# OpenROV_Controller_2_5B.net
KiCad netlist of a schematic drawn in EAGLE
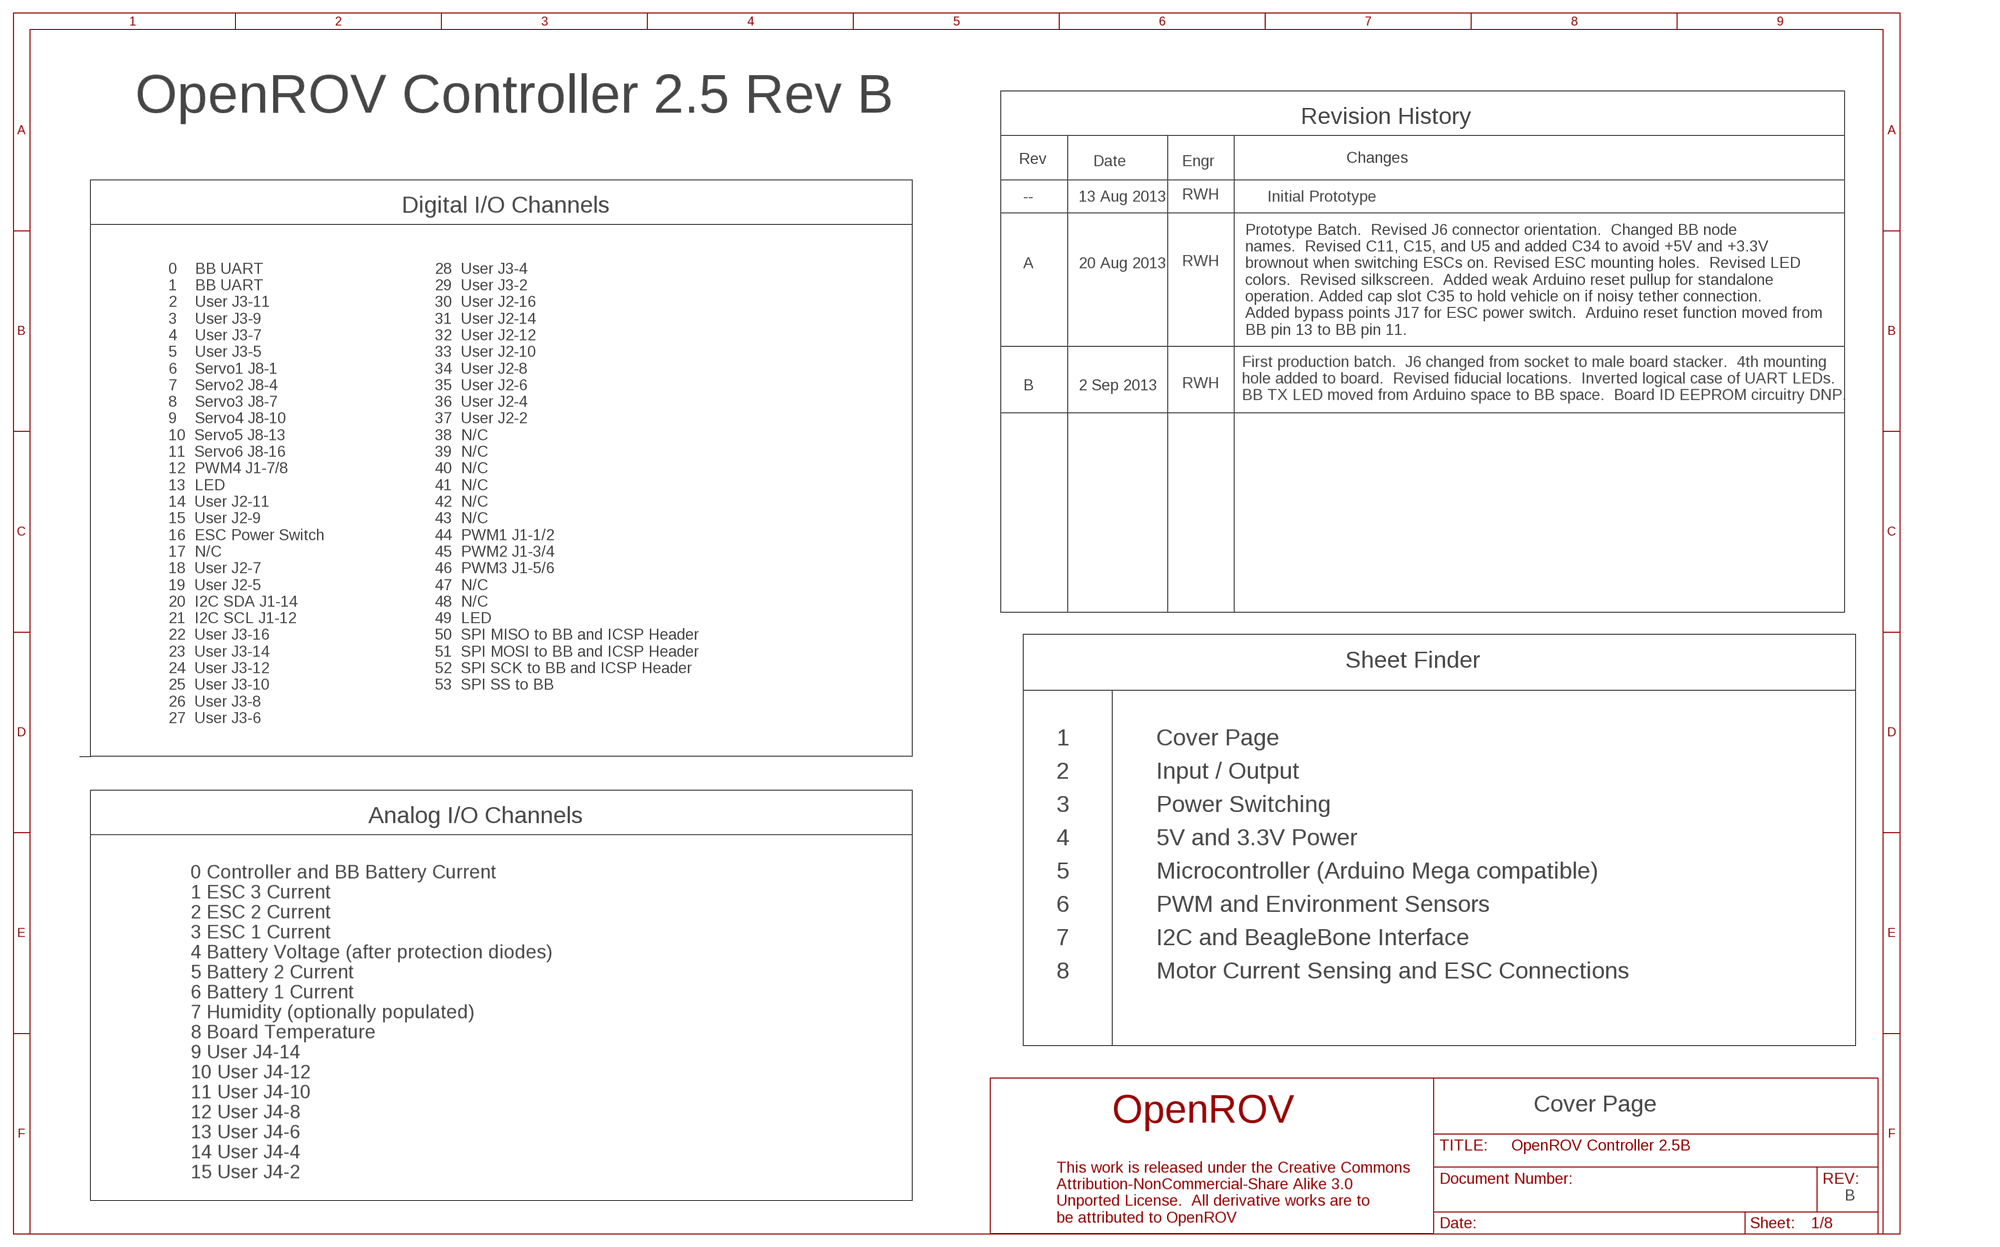
[diagram p0: schematic, sheet 1]
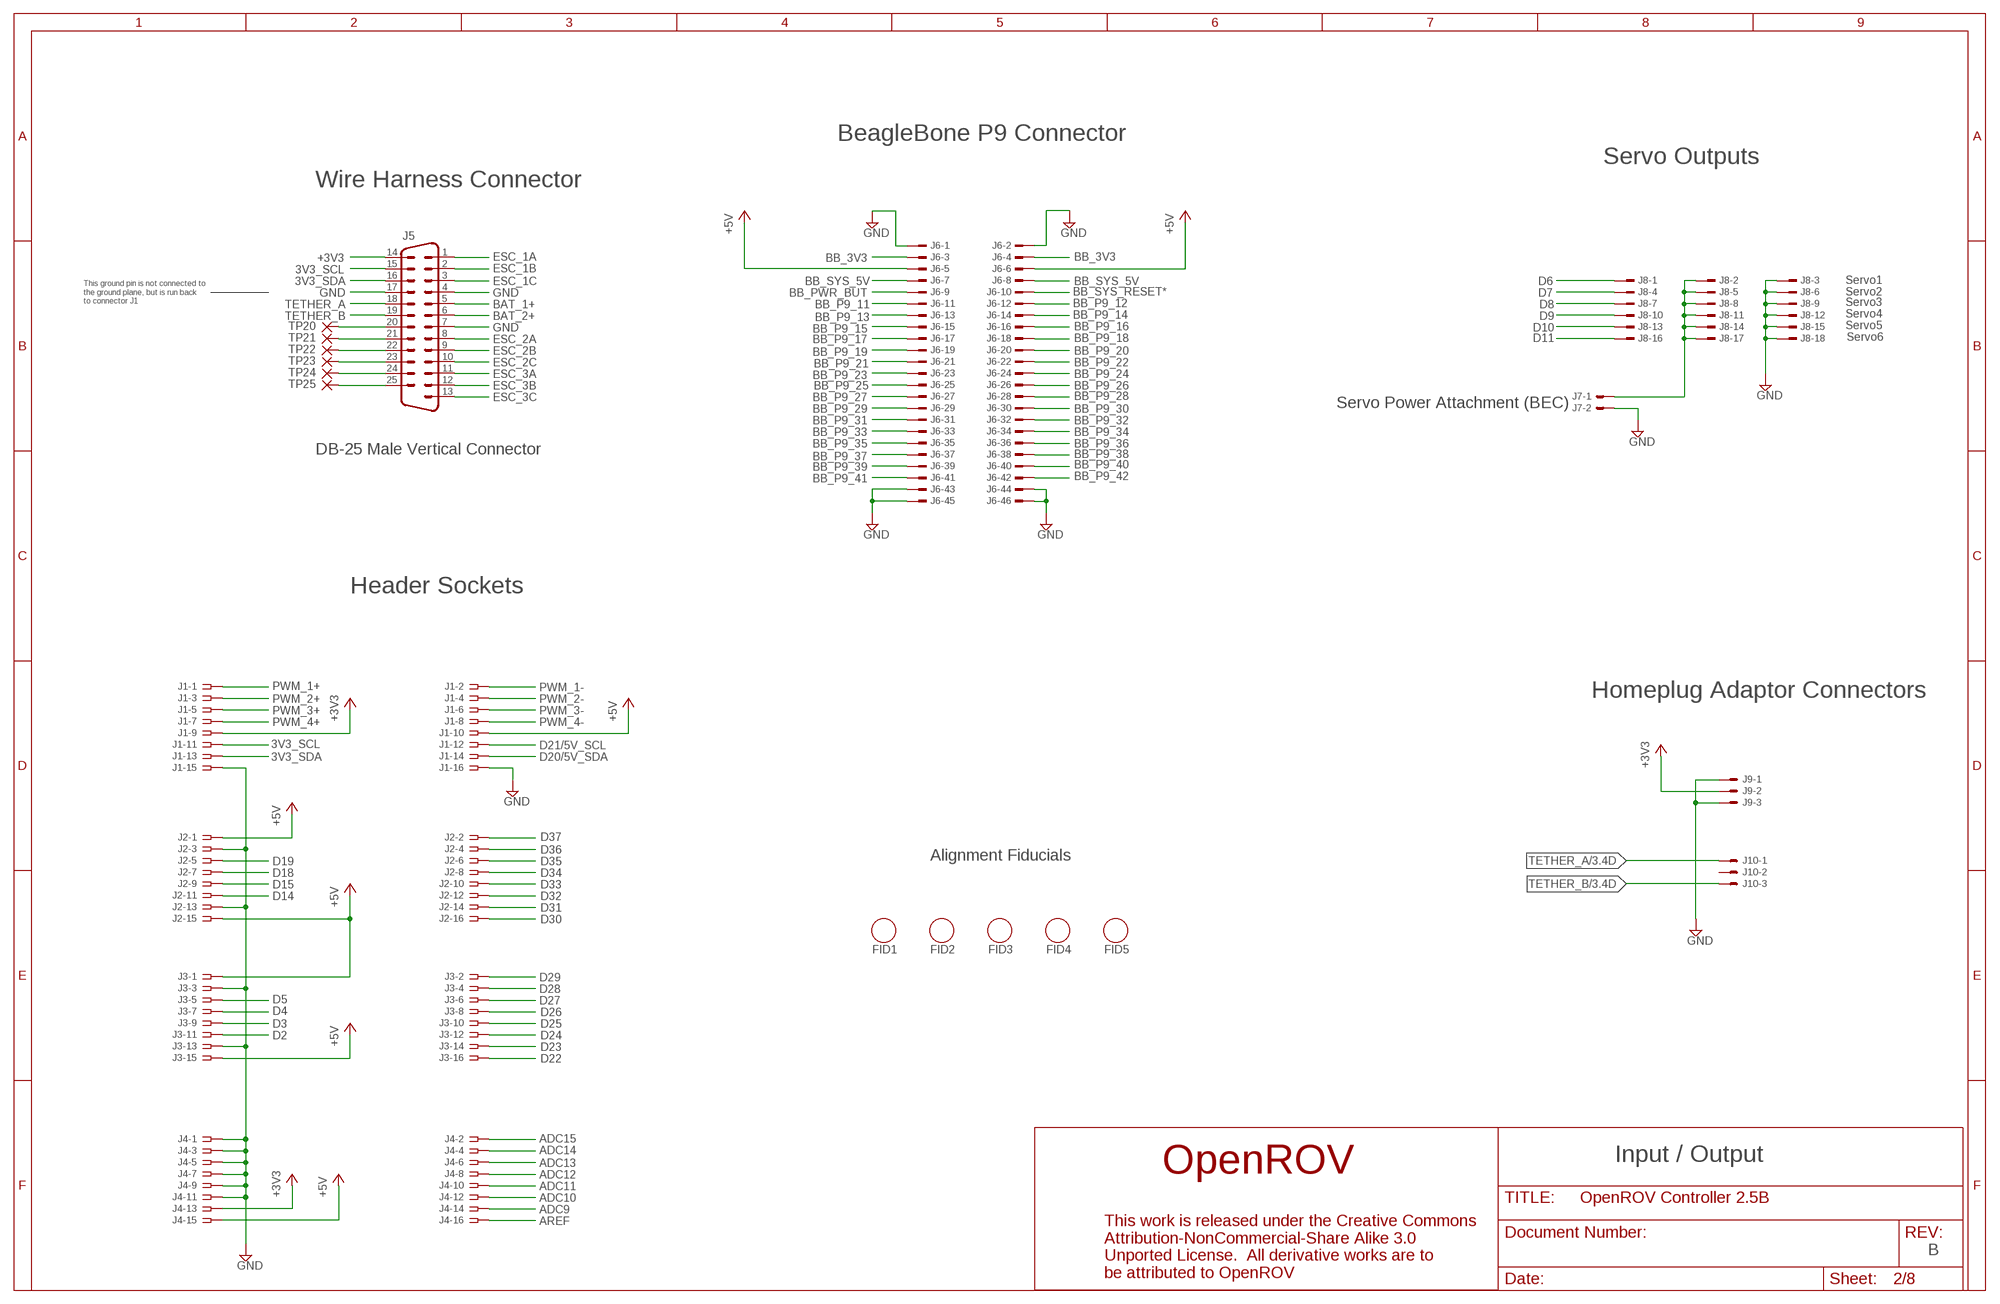
[diagram p1: schematic, sheet 2]
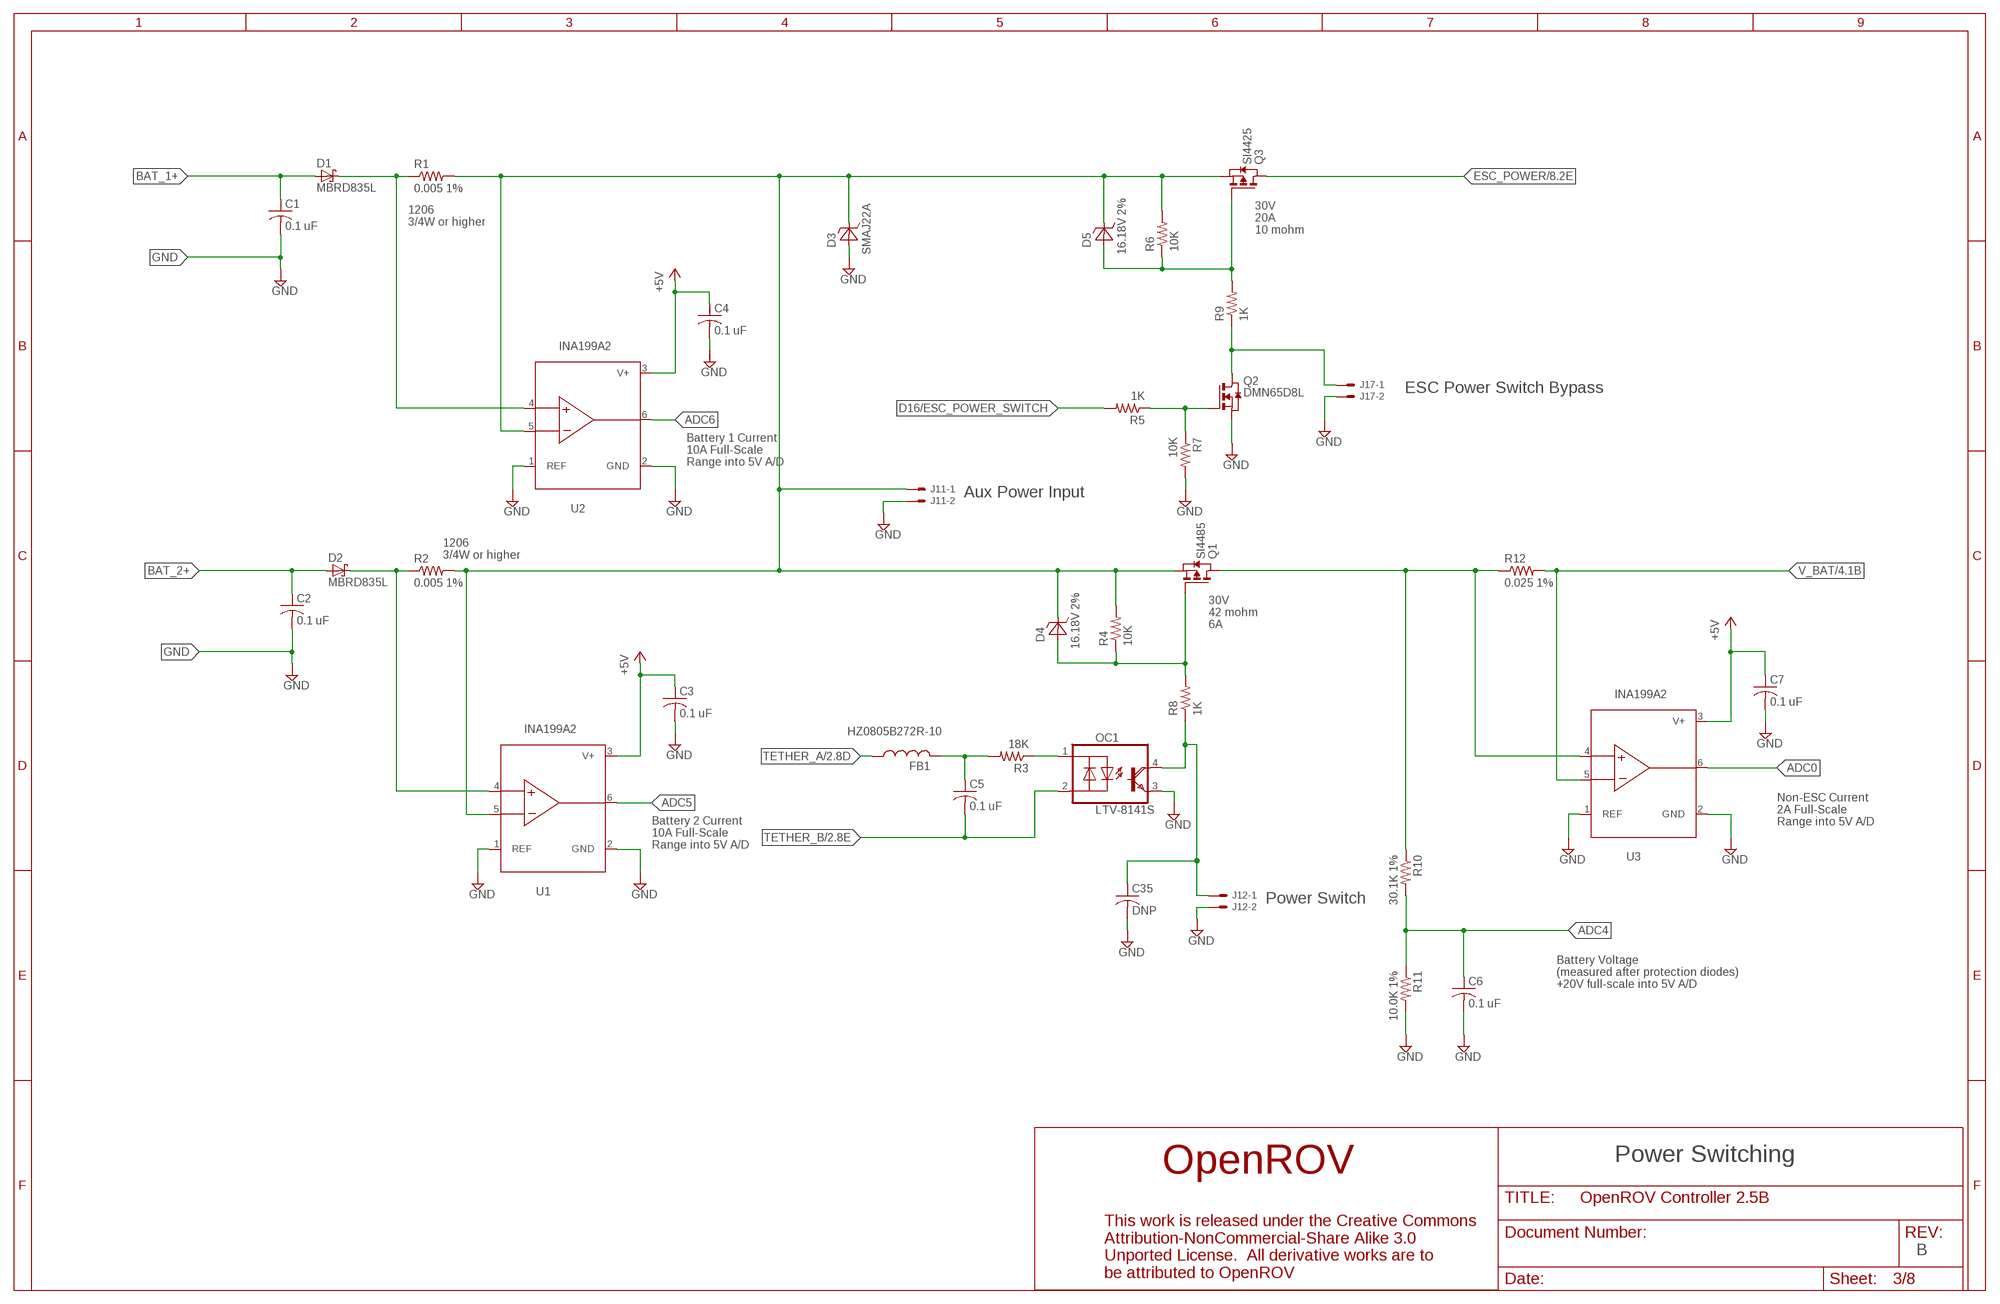
[diagram p2: schematic, sheet 3]
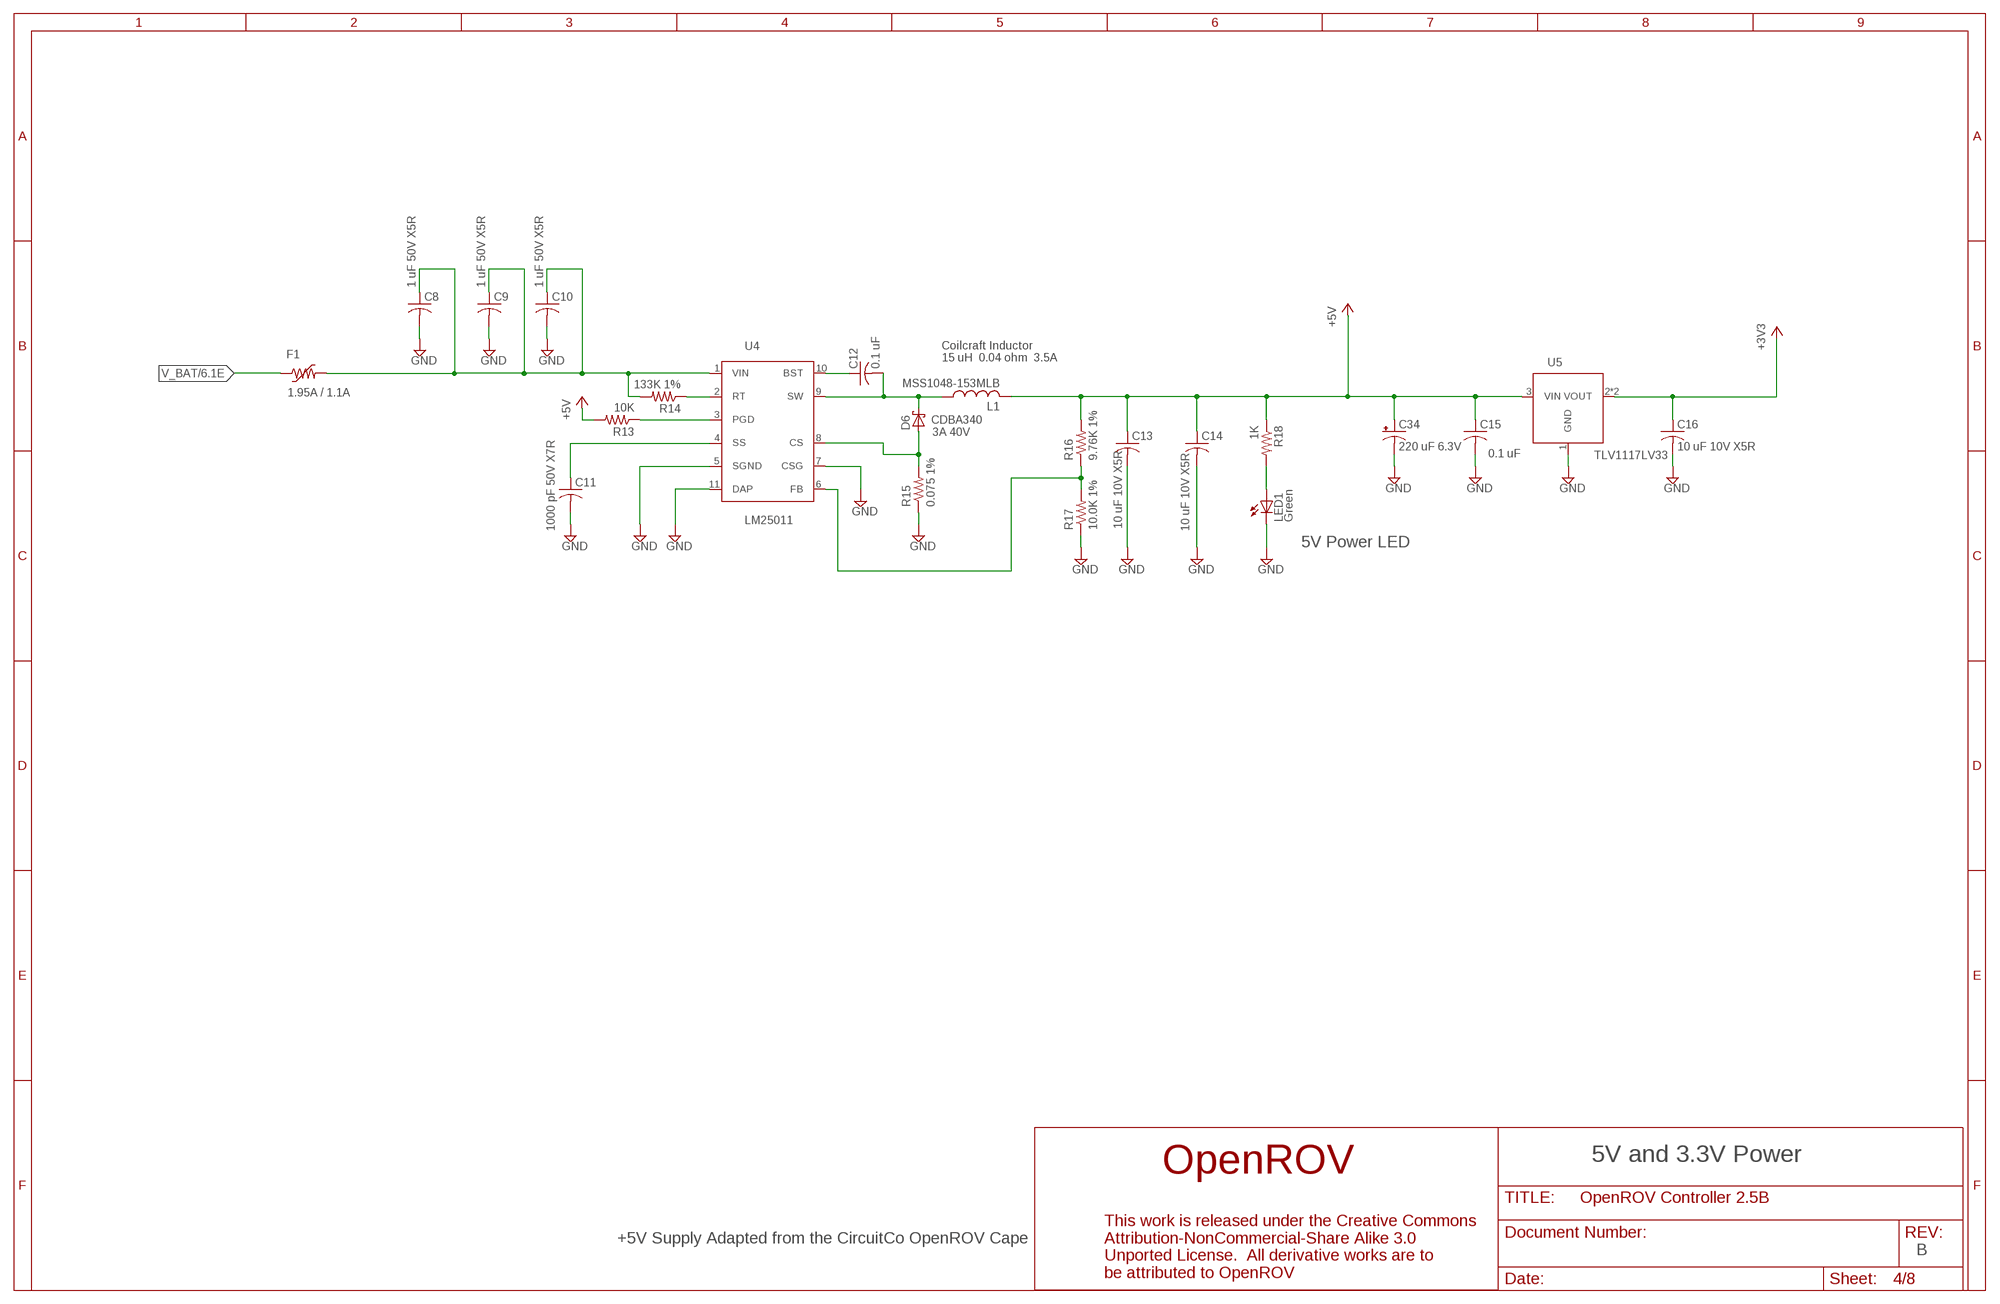
[diagram p3: schematic, sheet 4]
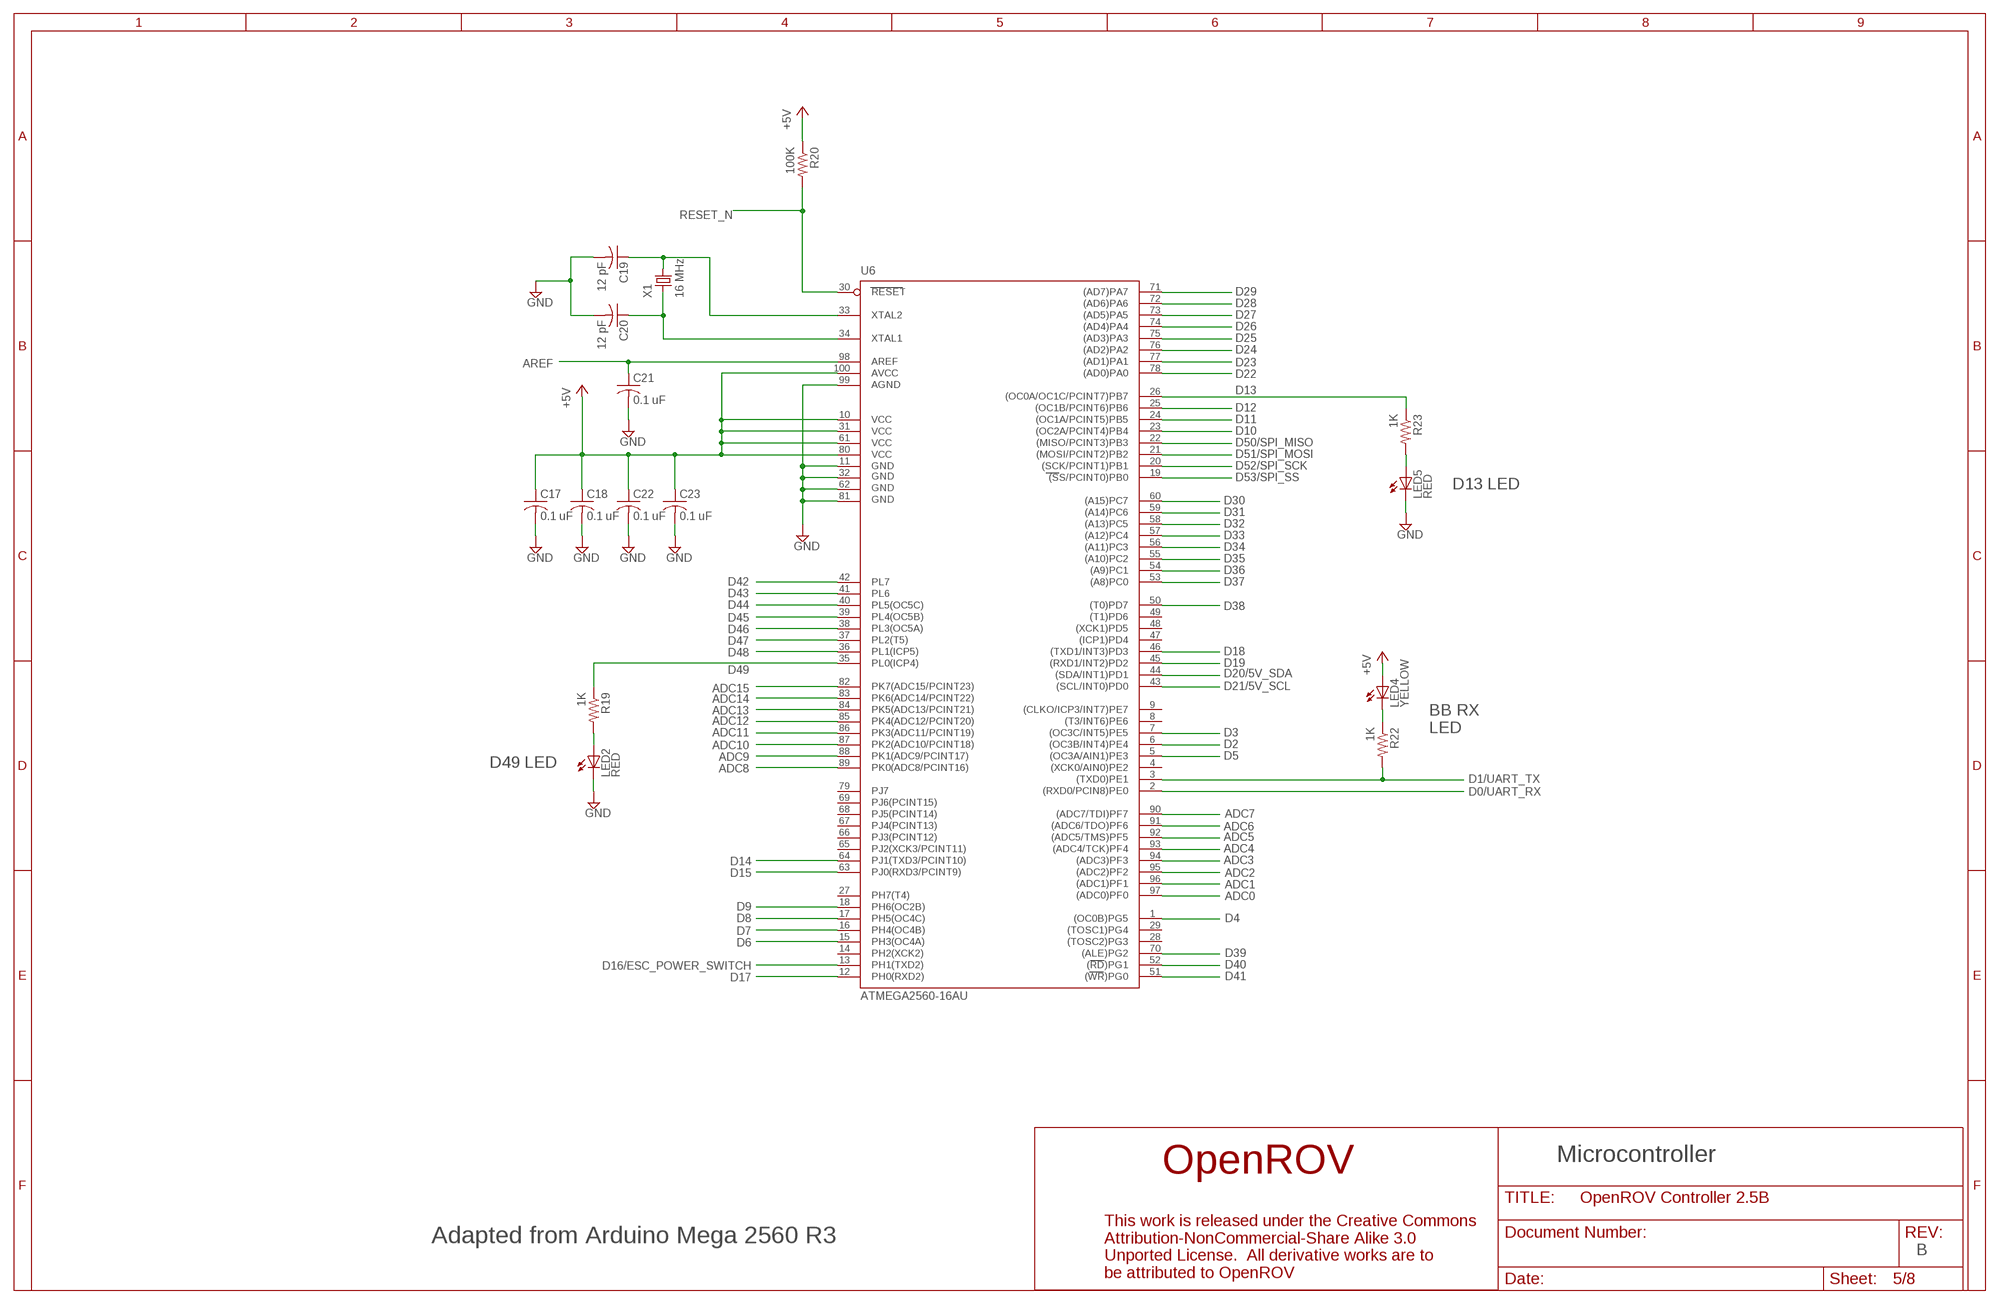
[diagram p4: schematic, sheet 5]
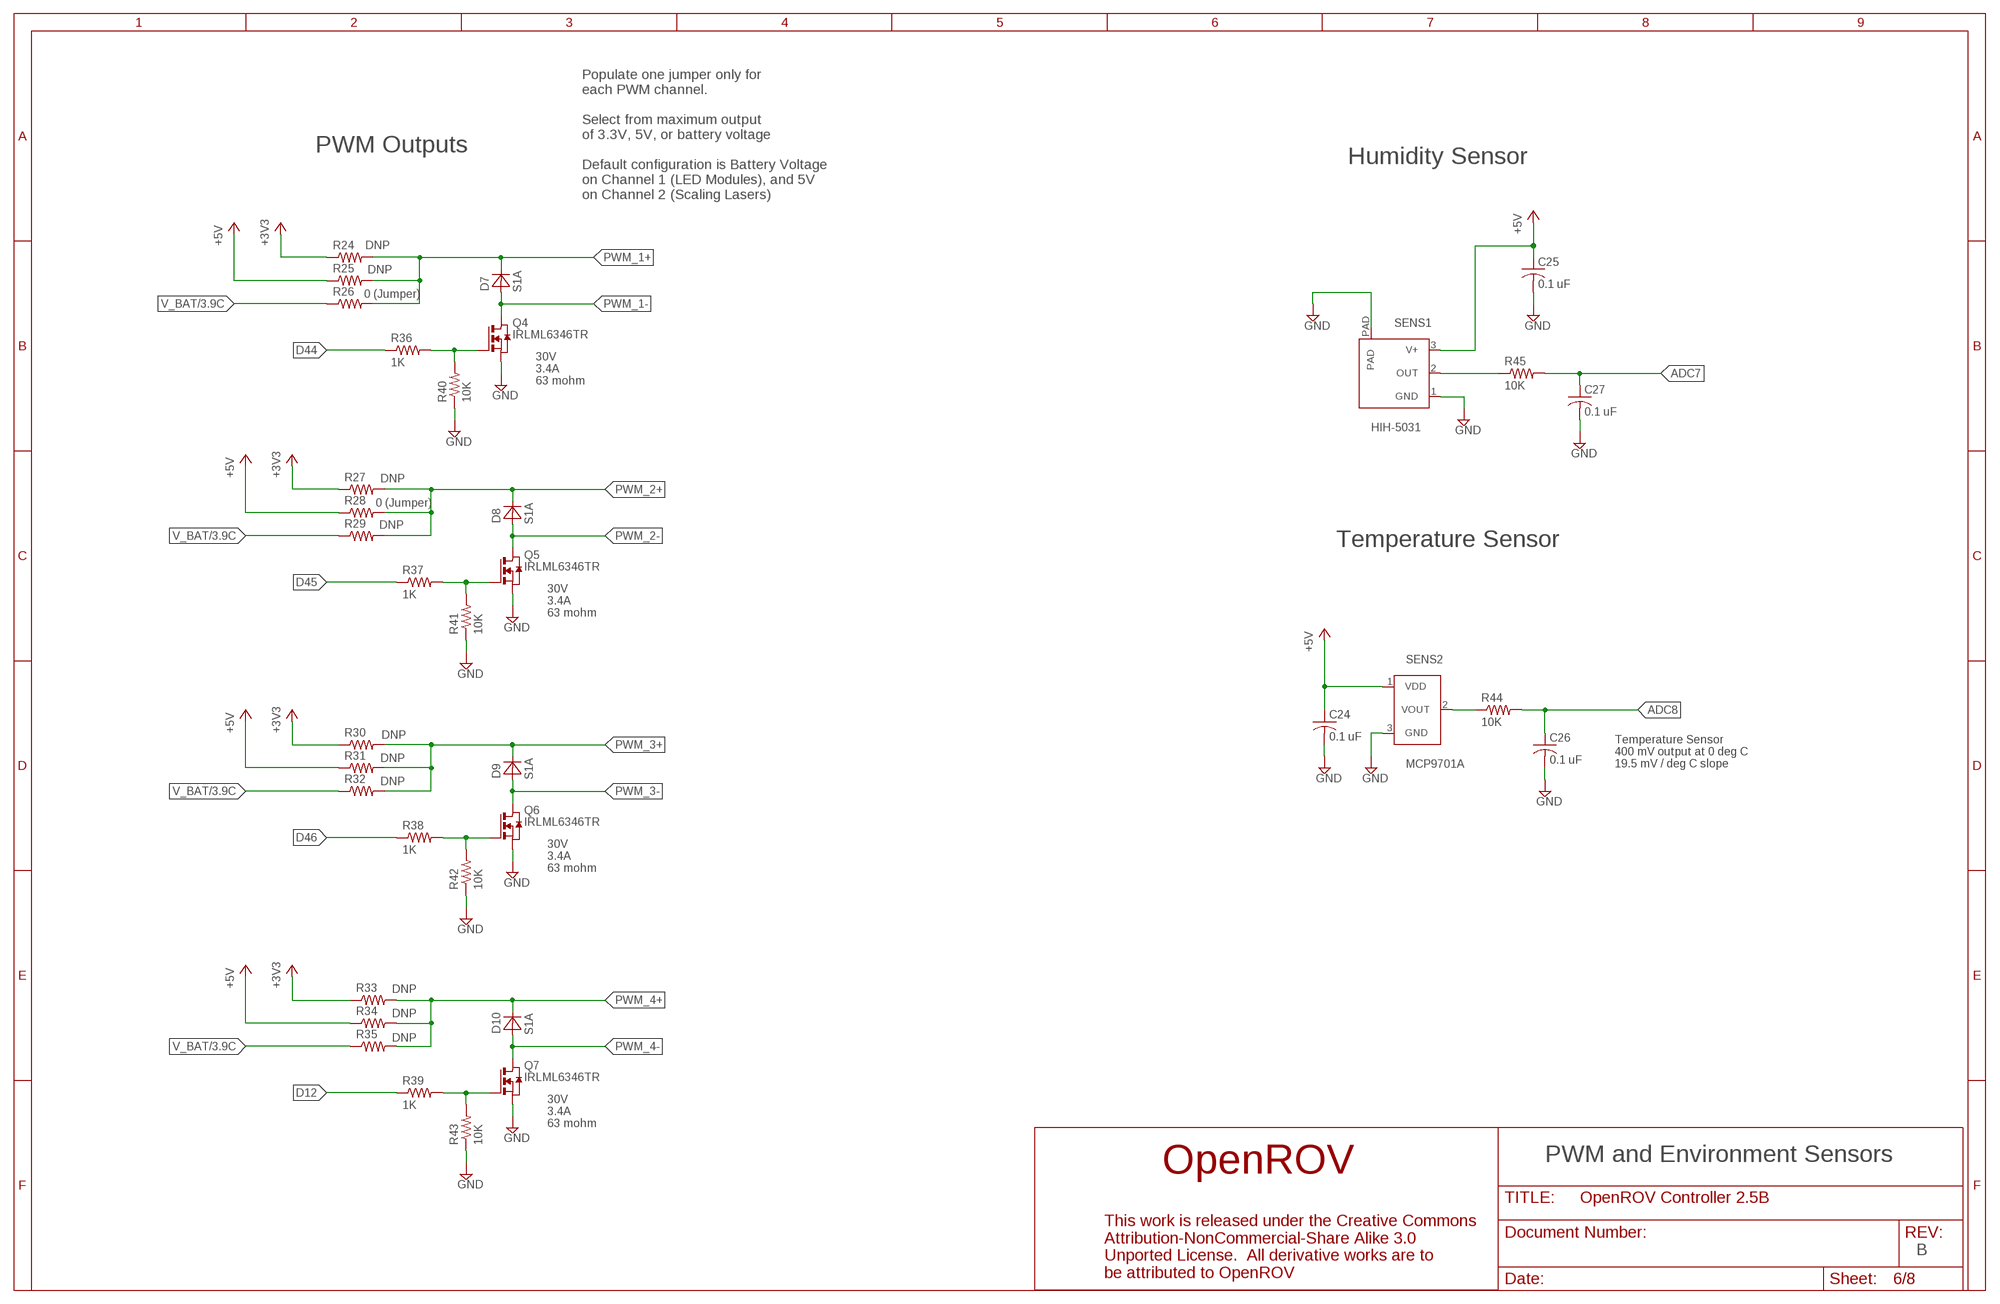
[diagram p5: schematic, sheet 6]
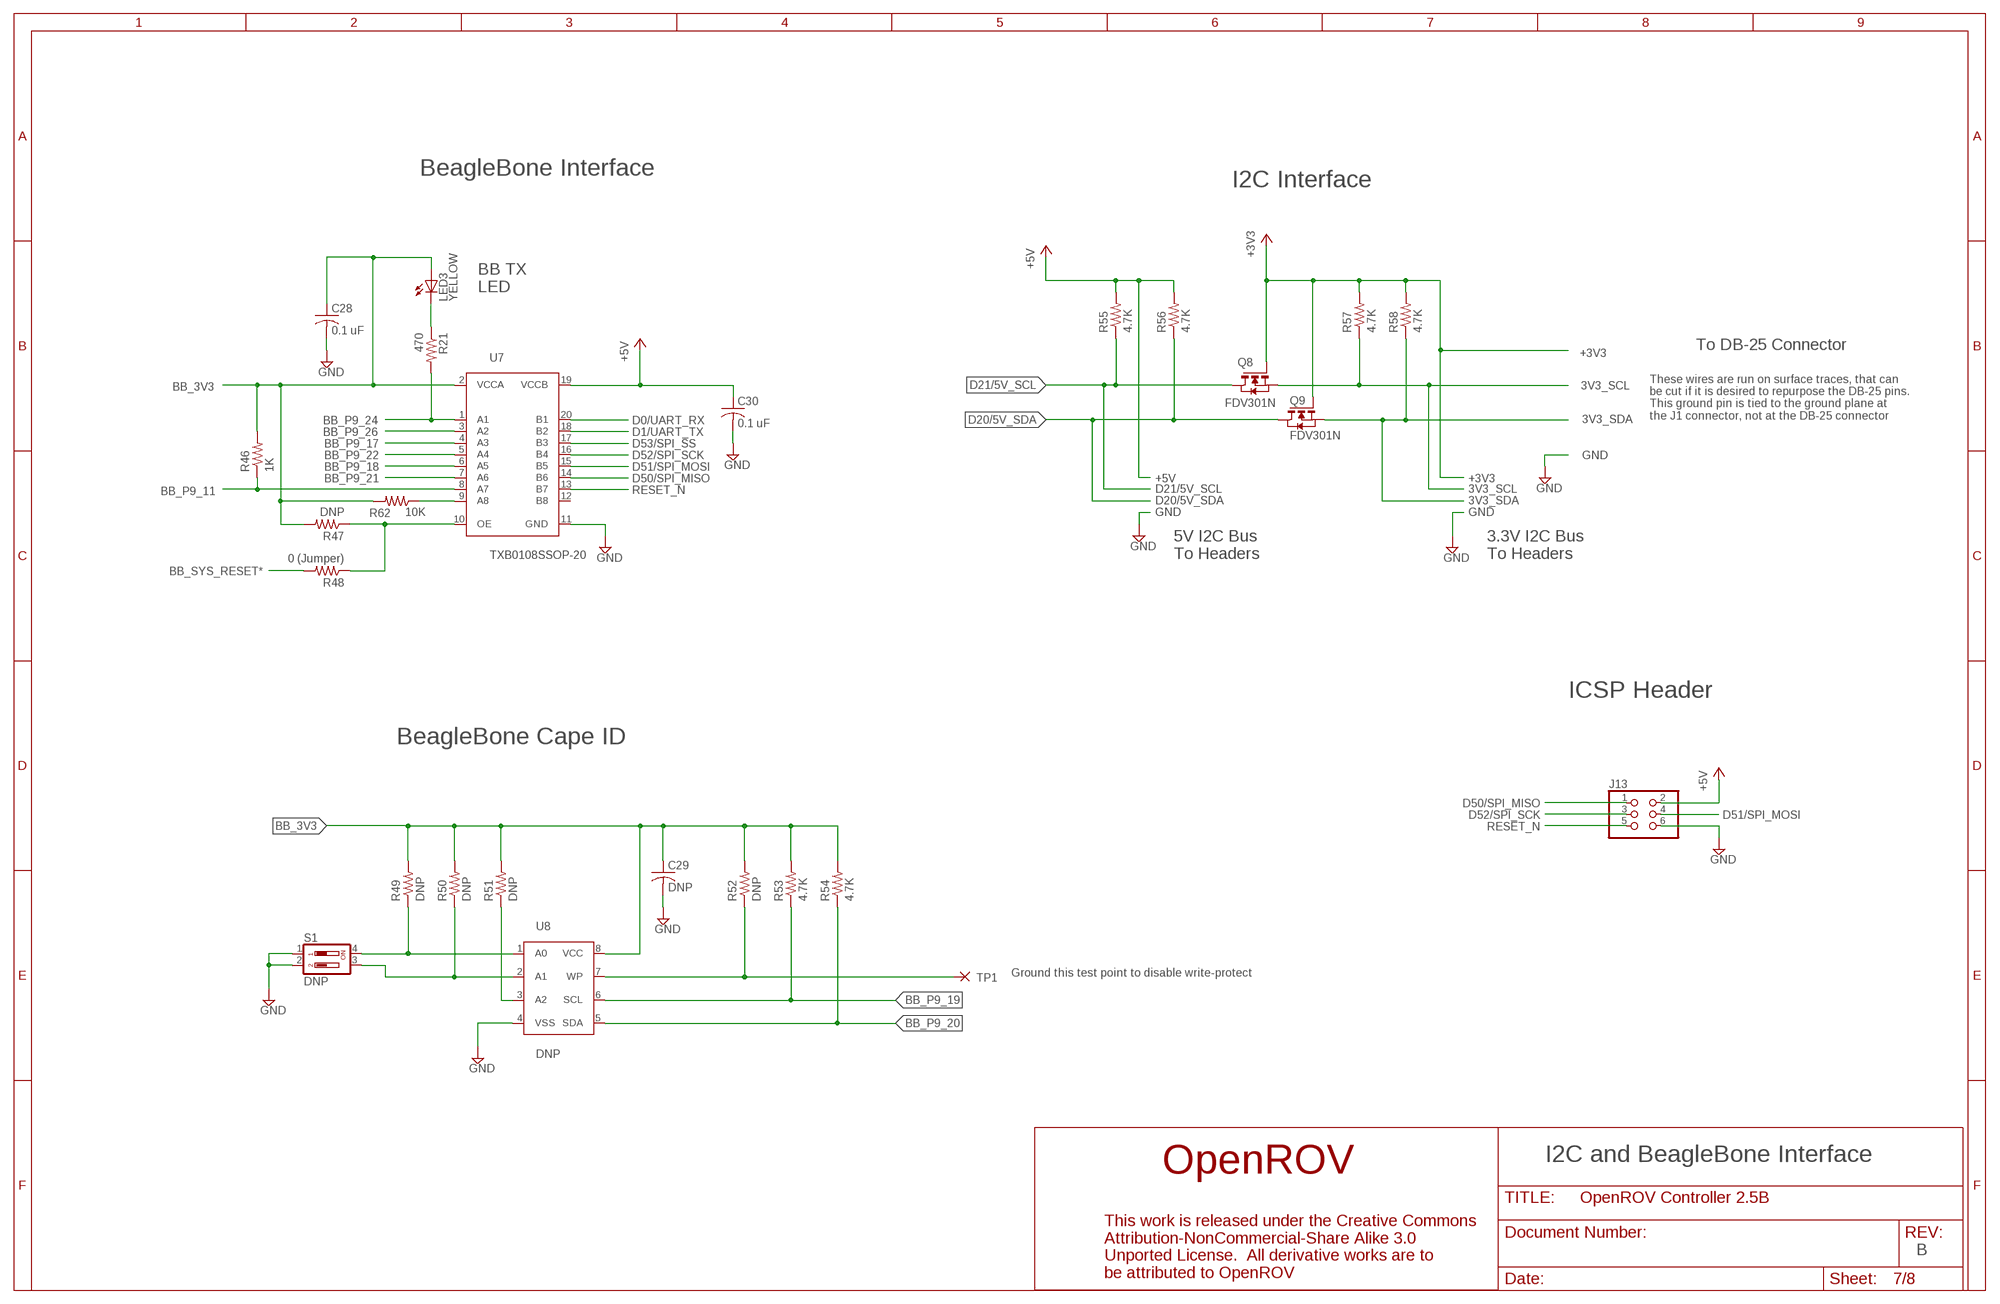
[diagram p6: schematic, sheet 7]
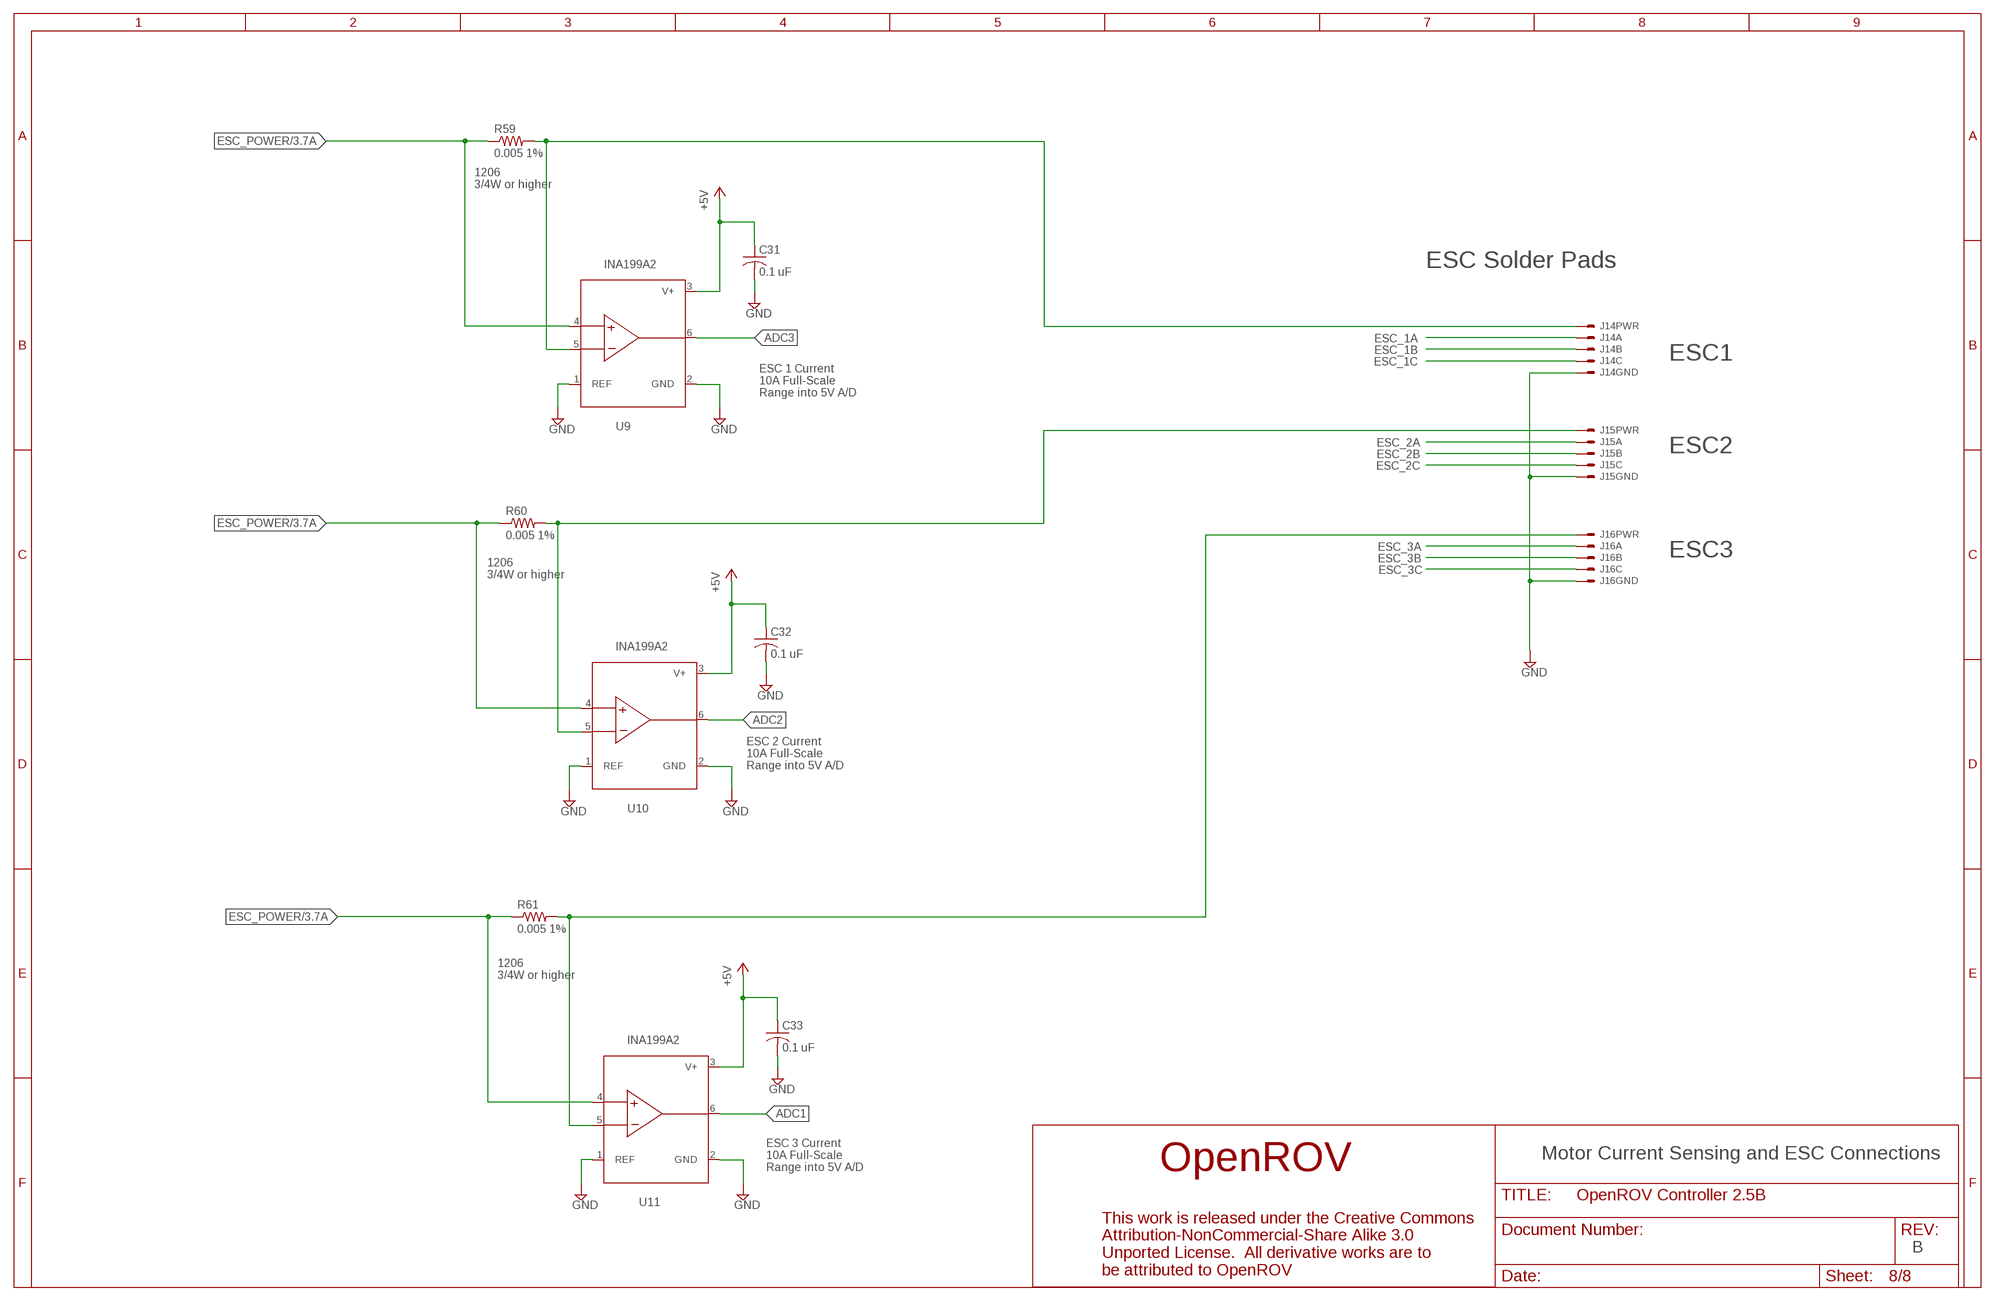
[diagram p7: schematic, sheet 8]

(export (version "E")
  (design (tool "Eeschema 10.0.6"))
  (components
    (comp (ref "C28")
      (value "0.1 uF")
      (footprint "eagle-import:R0603")
      (libsource (lib "eagle-import") (part "CAP0603"))
    )
    (comp (ref "C29")
      (value "DNP")
      (footprint "eagle-import:R0603")
      (libsource (lib "eagle-import") (part "CAP0603"))
    )
    (comp (ref "C30")
      (value "0.1 uF")
      (footprint "eagle-import:R0603")
      (libsource (lib "eagle-import") (part "CAP0603"))
    )
    (comp (ref "J13")
      (value "HDR_PINS_2X3")
      (footprint "eagle-import:HDR_PINS_2X3")
      (libsource (lib "eagle-import") (part "HDR_PINS_2X3"))
    )
    (comp (ref "LED3")
      (value "YELLOW")
      (footprint "eagle-import:LED_CHIPLED_0603")
      (libsource (lib "eagle-import") (part "LED-0603"))
    )
    (comp (ref "Q8")
      (value "FDV301N")
      (footprint "eagle-import:SOT23")
      (libsource (lib "eagle-import") (part "NMOS-FETSOT23"))
    )
    (comp (ref "Q9")
      (value "FDV301N")
      (footprint "eagle-import:SOT23")
      (libsource (lib "eagle-import") (part "NMOS-FETSOT23"))
    )
    (comp (ref "R21")
      (value "470")
      (footprint "eagle-import:R0603")
      (libsource (lib "eagle-import") (part "RESISTOR-0603"))
    )
    (comp (ref "R46")
      (value "1K")
      (footprint "eagle-import:R0603")
      (libsource (lib "eagle-import") (part "RESISTOR-0603"))
    )
    (comp (ref "R47")
      (value "DNP")
      (footprint "eagle-import:R0603")
      (libsource (lib "eagle-import") (part "RESISTOR-0603"))
    )
    (comp (ref "R48")
      (value "0 (Jumper)")
      (footprint "eagle-import:R0603")
      (libsource (lib "eagle-import") (part "RESISTOR-0603"))
    )
    (comp (ref "R49")
      (value "DNP")
      (footprint "eagle-import:R0603")
      (libsource (lib "eagle-import") (part "RESISTOR-0603"))
    )
    (comp (ref "R50")
      (value "DNP")
      (footprint "eagle-import:R0603")
      (libsource (lib "eagle-import") (part "RESISTOR-0603"))
    )
    (comp (ref "R51")
      (value "DNP")
      (footprint "eagle-import:R0603")
      (libsource (lib "eagle-import") (part "RESISTOR-0603"))
    )
    (comp (ref "R52")
      (value "DNP")
      (footprint "eagle-import:R0603")
      (libsource (lib "eagle-import") (part "RESISTOR-0603"))
    )
    (comp (ref "R53")
      (value "4.7K")
      (footprint "eagle-import:R0603")
      (libsource (lib "eagle-import") (part "RESISTOR-0603"))
    )
    (comp (ref "R54")
      (value "4.7K")
      (footprint "eagle-import:R0603")
      (libsource (lib "eagle-import") (part "RESISTOR-0603"))
    )
    (comp (ref "R55")
      (value "4.7K")
      (footprint "eagle-import:R0603")
      (libsource (lib "eagle-import") (part "RESISTOR-0603"))
    )
    (comp (ref "R56")
      (value "4.7K")
      (footprint "eagle-import:R0603")
      (libsource (lib "eagle-import") (part "RESISTOR-0603"))
    )
    (comp (ref "R57")
      (value "4.7K")
      (footprint "eagle-import:R0603")
      (libsource (lib "eagle-import") (part "RESISTOR-0603"))
    )
    (comp (ref "R58")
      (value "4.7K")
      (footprint "eagle-import:R0603")
      (libsource (lib "eagle-import") (part "RESISTOR-0603"))
    )
    (comp (ref "R62")
      (value "10K")
      (footprint "eagle-import:R0603")
      (libsource (lib "eagle-import") (part "RESISTOR-0603"))
    )
    (comp (ref "S1")
      (value "DNP")
      (footprint "eagle-import:CTS-219-02")
      (libsource (lib "eagle-import") (part "219-02"))
    )
    (comp (ref "TP1")
      (value "TEST_PAD-0.8S")
      (footprint "eagle-import:1.4_0.8")
      (libsource (lib "eagle-import") (part "TEST_PAD-0.8S"))
    )
    (comp (ref "U7")
      (value "TXB0108SSOP-20")
      (footprint "eagle-import:SSOP-20")
      (libsource (lib "eagle-import") (part "TXB0108SSOP-20"))
    )
    (comp (ref "U8")
      (value "DNP")
      (footprint "eagle-import:SO8")
      (libsource (lib "eagle-import") (part "CAT24C256WI-G"))
    )
    (comp (ref "C31")
      (value "0.1 uF")
      (footprint "eagle-import:R0603")
      (libsource (lib "eagle-import") (part "CAP0603"))
    )
    (comp (ref "C32")
      (value "0.1 uF")
      (footprint "eagle-import:R0603")
      (libsource (lib "eagle-import") (part "CAP0603"))
    )
    (comp (ref "C33")
      (value "0.1 uF")
      (footprint "eagle-import:R0603")
      (libsource (lib "eagle-import") (part "CAP0603"))
    )
    (comp (ref "J14")
      (value "ESC_PADS-0.156_ALT")
      (footprint "eagle-import:ESC-PADS-.156-ALT_SILK")
      (libsource (lib "eagle-import") (part "ESC_PADS-0.156_ALT"))
    )
    (comp (ref "J15")
      (value "ESC_PADS-0.156_ALT")
      (footprint "eagle-import:ESC-PADS-.156-ALT_SILK")
      (libsource (lib "eagle-import") (part "ESC_PADS-0.156_ALT"))
    )
    (comp (ref "J16")
      (value "ESC_PADS-0.156_ALT")
      (footprint "eagle-import:ESC-PADS-.156-ALT_SILK")
      (libsource (lib "eagle-import") (part "ESC_PADS-0.156_ALT"))
    )
    (comp (ref "R59")
      (value "0.005 1%")
      (footprint "eagle-import:R1206")
      (libsource (lib "eagle-import") (part "RESISTOR-1206"))
    )
    (comp (ref "R60")
      (value "0.005 1%")
      (footprint "eagle-import:R1206")
      (libsource (lib "eagle-import") (part "RESISTOR-1206"))
    )
    (comp (ref "R61")
      (value "0.005 1%")
      (footprint "eagle-import:R1206")
      (libsource (lib "eagle-import") (part "RESISTOR-1206"))
    )
    (comp (ref "U9")
      (value "INA199A2")
      (footprint "eagle-import:SC70-6L")
      (libsource (lib "eagle-import") (part "INA199"))
    )
    (comp (ref "U10")
      (value "INA199A2")
      (footprint "eagle-import:SC70-6L")
      (libsource (lib "eagle-import") (part "INA199"))
    )
    (comp (ref "U11")
      (value "INA199A2")
      (footprint "eagle-import:SC70-6L")
      (libsource (lib "eagle-import") (part "INA199"))
    )
    (comp (ref "C1")
      (value "0.1 uF")
      (footprint "eagle-import:R0603")
      (libsource (lib "eagle-import") (part "CAP0603"))
    )
    (comp (ref "C2")
      (value "0.1 uF")
      (footprint "eagle-import:R0603")
      (libsource (lib "eagle-import") (part "CAP0603"))
    )
    (comp (ref "C3")
      (value "0.1 uF")
      (footprint "eagle-import:R0603")
      (libsource (lib "eagle-import") (part "CAP0603"))
    )
    (comp (ref "C4")
      (value "0.1 uF")
      (footprint "eagle-import:R0603")
      (libsource (lib "eagle-import") (part "CAP0603"))
    )
    (comp (ref "C5")
      (value "0.1 uF")
      (footprint "eagle-import:R0603")
      (libsource (lib "eagle-import") (part "CAP0603"))
    )
    (comp (ref "C6")
      (value "0.1 uF")
      (footprint "eagle-import:R0603")
      (libsource (lib "eagle-import") (part "CAP0603"))
    )
    (comp (ref "C7")
      (value "0.1 uF")
      (footprint "eagle-import:R0603")
      (libsource (lib "eagle-import") (part "CAP0603"))
    )
    (comp (ref "C35")
      (value "DNP")
      (footprint "eagle-import:R0805")
      (libsource (lib "eagle-import") (part "CAP0805"))
    )
    (comp (ref "D1")
      (value "MBRD835L")
      (footprint "eagle-import:DPAK")
      (libsource (lib "eagle-import") (part "SCHOTTKYDPAK"))
    )
    (comp (ref "D2")
      (value "MBRD835L")
      (footprint "eagle-import:DPAK")
      (libsource (lib "eagle-import") (part "SCHOTTKYDPAK"))
    )
    (comp (ref "D3")
      (value "SMAJ22A")
      (footprint "eagle-import:DO214AC")
      (libsource (lib "eagle-import") (part "ZENER-TVSDO-214AC"))
    )
    (comp (ref "D4")
      (value "16.18V 2%")
      (footprint "eagle-import:SOD323")
      (libsource (lib "eagle-import") (part "ZENER-TVSSOD323"))
    )
    (comp (ref "D5")
      (value "16.18V 2%")
      (footprint "eagle-import:SOD323")
      (libsource (lib "eagle-import") (part "ZENER-TVSSOD323"))
    )
    (comp (ref "FB1")
      (value "HZ0805B272R-10")
      (footprint "eagle-import:R0805")
      (libsource (lib "eagle-import") (part "FERRITESIZE_0805"))
    )
    (comp (ref "J11")
      (value "HDR_1X2X0.100-ALT_SILK")
      (footprint "eagle-import:22-23-2021_ALT_SILK")
      (libsource (lib "eagle-import") (part "HDR_1X2X0.100-ALT_SILK"))
    )
    (comp (ref "J12")
      (value "HDR_1X2X0.100-ALT_SILK")
      (footprint "eagle-import:22-23-2021_ALT_SILK")
      (libsource (lib "eagle-import") (part "HDR_1X2X0.100-ALT_SILK"))
    )
    (comp (ref "J17")
      (value "HDR_1X2X0.100-ALT_SILK")
      (footprint "eagle-import:22-23-2021_ALT_SILK")
      (libsource (lib "eagle-import") (part "HDR_1X2X0.100-ALT_SILK"))
    )
    (comp (ref "OC1")
      (value "LTV-8141S")
      (footprint "eagle-import:DIL4-SMD")
      (libsource (lib "eagle-import") (part "LTV-8141S"))
    )
    (comp (ref "Q1")
      (value "SI4485")
      (footprint "eagle-import:SO8")
      (libsource (lib "eagle-import") (part "PMOS-FET"))
    )
    (comp (ref "Q2")
      (value "DMN65D8L")
      (footprint "eagle-import:SOT23")
      (libsource (lib "eagle-import") (part "NMOS-FETSOT23"))
    )
    (comp (ref "Q3")
      (value "SI4425")
      (footprint "eagle-import:SO8")
      (libsource (lib "eagle-import") (part "PMOS-FET"))
    )
    (comp (ref "R1")
      (value "0.005 1%")
      (footprint "eagle-import:R1206")
      (libsource (lib "eagle-import") (part "RESISTOR-1206"))
    )
    (comp (ref "R2")
      (value "0.005 1%")
      (footprint "eagle-import:R1206")
      (libsource (lib "eagle-import") (part "RESISTOR-1206"))
    )
    (comp (ref "R3")
      (value "18K")
      (footprint "eagle-import:R0603")
      (libsource (lib "eagle-import") (part "RESISTOR-0603"))
    )
    (comp (ref "R4")
      (value "10K")
      (footprint "eagle-import:R0603")
      (libsource (lib "eagle-import") (part "RESISTOR-0603"))
    )
    (comp (ref "R5")
      (value "1K")
      (footprint "eagle-import:R0603")
      (libsource (lib "eagle-import") (part "RESISTOR-0603"))
    )
    (comp (ref "R6")
      (value "10K")
      (footprint "eagle-import:R0603")
      (libsource (lib "eagle-import") (part "RESISTOR-0603"))
    )
    (comp (ref "R7")
      (value "10K")
      (footprint "eagle-import:R0603")
      (libsource (lib "eagle-import") (part "RESISTOR-0603"))
    )
    (comp (ref "R8")
      (value "1K")
      (footprint "eagle-import:R0603")
      (libsource (lib "eagle-import") (part "RESISTOR-0603"))
    )
    (comp (ref "R9")
      (value "1K")
      (footprint "eagle-import:R0603")
      (libsource (lib "eagle-import") (part "RESISTOR-0603"))
    )
    (comp (ref "R10")
      (value "30.1K 1%")
      (footprint "eagle-import:R0603")
      (libsource (lib "eagle-import") (part "RESISTOR-0603"))
    )
    (comp (ref "R11")
      (value "10.0K 1%")
      (footprint "eagle-import:R0603")
      (libsource (lib "eagle-import") (part "RESISTOR-0603"))
    )
    (comp (ref "R12")
      (value "0.025 1%")
      (footprint "eagle-import:R0805")
      (libsource (lib "eagle-import") (part "RESISTOR-0805"))
    )
    (comp (ref "U1")
      (value "INA199A2")
      (footprint "eagle-import:SC70-6L")
      (libsource (lib "eagle-import") (part "INA199"))
    )
    (comp (ref "U2")
      (value "INA199A2")
      (footprint "eagle-import:SC70-6L")
      (libsource (lib "eagle-import") (part "INA199"))
    )
    (comp (ref "U3")
      (value "INA199A2")
      (footprint "eagle-import:SC70-6L")
      (libsource (lib "eagle-import") (part "INA199"))
    )
    (comp (ref "C24")
      (value "0.1 uF")
      (footprint "eagle-import:R0603")
      (libsource (lib "eagle-import") (part "CAP0603"))
    )
    (comp (ref "C25")
      (value "0.1 uF")
      (footprint "eagle-import:R0603")
      (libsource (lib "eagle-import") (part "CAP0603"))
    )
    (comp (ref "C26")
      (value "0.1 uF")
      (footprint "eagle-import:R0603")
      (libsource (lib "eagle-import") (part "CAP0603"))
    )
    (comp (ref "C27")
      (value "0.1 uF")
      (footprint "eagle-import:R0603")
      (libsource (lib "eagle-import") (part "CAP0603"))
    )
    (comp (ref "D7")
      (value "S1A")
      (footprint "eagle-import:DO214AC")
      (libsource (lib "eagle-import") (part "DIODE"))
    )
    (comp (ref "D8")
      (value "S1A")
      (footprint "eagle-import:DO214AC")
      (libsource (lib "eagle-import") (part "DIODE"))
    )
    (comp (ref "D9")
      (value "S1A")
      (footprint "eagle-import:DO214AC")
      (libsource (lib "eagle-import") (part "DIODE"))
    )
    (comp (ref "D10")
      (value "S1A")
      (footprint "eagle-import:DO214AC")
      (libsource (lib "eagle-import") (part "DIODE"))
    )
    (comp (ref "Q4")
      (value "IRLML6346TR")
      (footprint "eagle-import:SOT23")
      (libsource (lib "eagle-import") (part "NMOS-FETSOT23"))
    )
    (comp (ref "Q5")
      (value "IRLML6346TR")
      (footprint "eagle-import:SOT23")
      (libsource (lib "eagle-import") (part "NMOS-FETSOT23"))
    )
    (comp (ref "Q6")
      (value "IRLML6346TR")
      (footprint "eagle-import:SOT23")
      (libsource (lib "eagle-import") (part "NMOS-FETSOT23"))
    )
    (comp (ref "Q7")
      (value "IRLML6346TR")
      (footprint "eagle-import:SOT23")
      (libsource (lib "eagle-import") (part "NMOS-FETSOT23"))
    )
    (comp (ref "R24")
      (value "DNP")
      (footprint "eagle-import:R0603")
      (libsource (lib "eagle-import") (part "RESISTOR-0603"))
    )
    (comp (ref "R25")
      (value "DNP")
      (footprint "eagle-import:R0603")
      (libsource (lib "eagle-import") (part "RESISTOR-0603"))
    )
    (comp (ref "R26")
      (value "0 (Jumper)")
      (footprint "eagle-import:R0603")
      (libsource (lib "eagle-import") (part "RESISTOR-0603"))
    )
    (comp (ref "R27")
      (value "DNP")
      (footprint "eagle-import:R0603")
      (libsource (lib "eagle-import") (part "RESISTOR-0603"))
    )
    (comp (ref "R28")
      (value "0 (Jumper)")
      (footprint "eagle-import:R0603")
      (libsource (lib "eagle-import") (part "RESISTOR-0603"))
    )
    (comp (ref "R29")
      (value "DNP")
      (footprint "eagle-import:R0603")
      (libsource (lib "eagle-import") (part "RESISTOR-0603"))
    )
    (comp (ref "R30")
      (value "DNP")
      (footprint "eagle-import:R0603")
      (libsource (lib "eagle-import") (part "RESISTOR-0603"))
    )
    (comp (ref "R31")
      (value "DNP")
      (footprint "eagle-import:R0603")
      (libsource (lib "eagle-import") (part "RESISTOR-0603"))
    )
    (comp (ref "R32")
      (value "DNP")
      (footprint "eagle-import:R0603")
      (libsource (lib "eagle-import") (part "RESISTOR-0603"))
    )
    (comp (ref "R33")
      (value "DNP")
      (footprint "eagle-import:R0603")
      (libsource (lib "eagle-import") (part "RESISTOR-0603"))
    )
    (comp (ref "R34")
      (value "DNP")
      (footprint "eagle-import:R0603")
      (libsource (lib "eagle-import") (part "RESISTOR-0603"))
    )
    (comp (ref "R35")
      (value "DNP")
      (footprint "eagle-import:R0603")
      (libsource (lib "eagle-import") (part "RESISTOR-0603"))
    )
    (comp (ref "R36")
      (value "1K")
      (footprint "eagle-import:R0603")
      (libsource (lib "eagle-import") (part "RESISTOR-0603"))
    )
    (comp (ref "R37")
      (value "1K")
      (footprint "eagle-import:R0603")
      (libsource (lib "eagle-import") (part "RESISTOR-0603"))
    )
    (comp (ref "R38")
      (value "1K")
      (footprint "eagle-import:R0603")
      (libsource (lib "eagle-import") (part "RESISTOR-0603"))
    )
    (comp (ref "R39")
      (value "1K")
      (footprint "eagle-import:R0603")
      (libsource (lib "eagle-import") (part "RESISTOR-0603"))
    )
    (comp (ref "R40")
      (value "10K")
      (footprint "eagle-import:R0603")
      (libsource (lib "eagle-import") (part "RESISTOR-0603"))
    )
    (comp (ref "R41")
      (value "10K")
      (footprint "eagle-import:R0603")
      (libsource (lib "eagle-import") (part "RESISTOR-0603"))
    )
    (comp (ref "R42")
      (value "10K")
      (footprint "eagle-import:R0603")
      (libsource (lib "eagle-import") (part "RESISTOR-0603"))
    )
    (comp (ref "R43")
      (value "10K")
      (footprint "eagle-import:R0603")
      (libsource (lib "eagle-import") (part "RESISTOR-0603"))
    )
    (comp (ref "R44")
      (value "10K")
      (footprint "eagle-import:R0603")
      (libsource (lib "eagle-import") (part "RESISTOR-0603"))
    )
    (comp (ref "R45")
      (value "10K")
      (footprint "eagle-import:R0603")
      (libsource (lib "eagle-import") (part "RESISTOR-0603"))
    )
    (comp (ref "SENS1")
      (value "HIH-5031")
      (footprint "eagle-import:HIH-5031")
      (libsource (lib "eagle-import") (part "HIH-5031"))
    )
    (comp (ref "SENS2")
      (value "MCP9701A")
      (footprint "eagle-import:SOT23")
      (libsource (lib "eagle-import") (part "MCP9701"))
    )
    (comp (ref "FID1")
      (value "FIDUCIAL_1")
      (footprint "eagle-import:FIDUCIAL_1")
      (libsource (lib "eagle-import") (part "FIDUCIAL_1"))
    )
    (comp (ref "FID2")
      (value "FIDUCIAL_1")
      (footprint "eagle-import:FIDUCIAL_1")
      (libsource (lib "eagle-import") (part "FIDUCIAL_1"))
    )
    (comp (ref "FID3")
      (value "FIDUCIAL_1")
      (footprint "eagle-import:FIDUCIAL_1")
      (libsource (lib "eagle-import") (part "FIDUCIAL_1"))
    )
    (comp (ref "FID4")
      (value "FIDUCIAL_1")
      (footprint "eagle-import:FIDUCIAL_1")
      (libsource (lib "eagle-import") (part "FIDUCIAL_1"))
    )
    (comp (ref "FID5")
      (value "FIDUCIAL_1")
      (footprint "eagle-import:FIDUCIAL_1")
      (libsource (lib "eagle-import") (part "FIDUCIAL_1"))
    )
    (comp (ref "J1")
      (value "HDR_SOCKET_2X8")
      (footprint "eagle-import:SSW-108-02-S-D")
      (fields (field (name "MPN") "SSW-108-02-S-D"))
      (libsource (lib "eagle-import") (part "HDR_SOCKET_2X8"))
    )
    (comp (ref "J2")
      (value "HDR_SOCKET_2X8")
      (footprint "eagle-import:SSW-108-02-S-D")
      (fields (field (name "MPN") "SSW-108-02-S-D"))
      (libsource (lib "eagle-import") (part "HDR_SOCKET_2X8"))
    )
    (comp (ref "J3")
      (value "HDR_SOCKET_2X8")
      (footprint "eagle-import:SSW-108-02-S-D")
      (fields (field (name "MPN") "SSW-108-02-S-D"))
      (libsource (lib "eagle-import") (part "HDR_SOCKET_2X8"))
    )
    (comp (ref "J4")
      (value "HDR_SOCKET_2X8")
      (footprint "eagle-import:SSW-108-02-S-D")
      (fields (field (name "MPN") "SSW-108-02-S-D"))
      (libsource (lib "eagle-import") (part "HDR_SOCKET_2X8"))
    )
    (comp (ref "J5")
      (value "M25VP")
      (footprint "eagle-import:M25VP")
      (libsource (lib "eagle-import") (part "M25VP"))
    )
    (comp (ref "J6")
      (value "BEAGLEBONE_PIN_HEADER")
      (footprint "eagle-import:TSW-123-02-S-D")
      (libsource (lib "eagle-import") (part "BEAGLEBONE_PIN_HEADER"))
    )
    (comp (ref "J7")
      (value "HDR_1X2X0.100-ALT_SILK")
      (footprint "eagle-import:22-23-2021_ALT_SILK")
      (libsource (lib "eagle-import") (part "HDR_1X2X0.100-ALT_SILK"))
    )
    (comp (ref "J8")
      (value "HDR_PINS_3X6")
      (footprint "eagle-import:HDR_PINS_3X6")
      (libsource (lib "eagle-import") (part "HDR_PINS_3X6"))
    )
    (comp (ref "J9")
      (value "HDR_1X3X0.100-ALT_SILK")
      (footprint "eagle-import:22-23-2031_ALT_SILK")
      (libsource (lib "eagle-import") (part "HDR_1X3X0.100-ALT_SILK"))
    )
    (comp (ref "J10")
      (value "HDR_1X3X0.100-ALT_SILK")
      (footprint "eagle-import:22-23-2031_ALT_SILK")
      (libsource (lib "eagle-import") (part "HDR_1X3X0.100-ALT_SILK"))
    )
    (comp (ref "TP20")
      (value "TEST_PAD-0.8S")
      (footprint "eagle-import:1.4_0.8")
      (libsource (lib "eagle-import") (part "TEST_PAD-0.8S"))
    )
    (comp (ref "TP21")
      (value "TEST_PAD-0.8S")
      (footprint "eagle-import:1.4_0.8")
      (libsource (lib "eagle-import") (part "TEST_PAD-0.8S"))
    )
    (comp (ref "TP22")
      (value "TEST_PAD-0.8S")
      (footprint "eagle-import:1.4_0.8")
      (libsource (lib "eagle-import") (part "TEST_PAD-0.8S"))
    )
    (comp (ref "TP23")
      (value "TEST_PAD-0.8S")
      (footprint "eagle-import:1.4_0.8")
      (libsource (lib "eagle-import") (part "TEST_PAD-0.8S"))
    )
    (comp (ref "TP24")
      (value "TEST_PAD-0.8S")
      (footprint "eagle-import:1.4_0.8")
      (libsource (lib "eagle-import") (part "TEST_PAD-0.8S"))
    )
    (comp (ref "TP25")
      (value "TEST_PAD-0.8S")
      (footprint "eagle-import:1.4_0.8")
      (libsource (lib "eagle-import") (part "TEST_PAD-0.8S"))
    )
    (comp (ref "C8")
      (value "1 uF 50V X5R")
      (footprint "eagle-import:R0805")
      (libsource (lib "eagle-import") (part "CAP0805"))
    )
    (comp (ref "C9")
      (value "1 uF 50V X5R")
      (footprint "eagle-import:R0805")
      (libsource (lib "eagle-import") (part "CAP0805"))
    )
    (comp (ref "C10")
      (value "1 uF 50V X5R")
      (footprint "eagle-import:R0805")
      (libsource (lib "eagle-import") (part "CAP0805"))
    )
    (comp (ref "C11")
      (value "1000 pF 50V X7R")
      (footprint "eagle-import:R0603")
      (libsource (lib "eagle-import") (part "CAP0603"))
    )
    (comp (ref "C12")
      (value "0.1 uF")
      (footprint "eagle-import:R0603")
      (libsource (lib "eagle-import") (part "CAP0603"))
    )
    (comp (ref "C13")
      (value "10 uF 10V X5R")
      (footprint "eagle-import:R0805")
      (libsource (lib "eagle-import") (part "CAP0805"))
    )
    (comp (ref "C14")
      (value "10 uF 10V X5R")
      (footprint "eagle-import:R0805")
      (libsource (lib "eagle-import") (part "CAP0805"))
    )
    (comp (ref "C15")
      (value "0.1 uF")
      (footprint "eagle-import:R0603")
      (libsource (lib "eagle-import") (part "CAP0603"))
    )
    (comp (ref "C16")
      (value "10 uF 10V X5R")
      (footprint "eagle-import:R0805")
      (libsource (lib "eagle-import") (part "CAP0805"))
    )
    (comp (ref "C34")
      (value "220 uF 6.3V")
      (footprint "eagle-import:KEMET_B-CAPACITOR")
      (libsource (lib "eagle-import") (part "CAP-POLARIZED-B_CASE"))
    )
    (comp (ref "D6")
      (value "CDBA340")
      (footprint "eagle-import:DO214AC")
      (libsource (lib "eagle-import") (part "SCHOTTKYDO214AC"))
    )
    (comp (ref "F1")
      (value "1.95A / 1.1A")
      (footprint "eagle-import:R1812")
      (libsource (lib "eagle-import") (part "POLYFUSE-1812"))
    )
    (comp (ref "L1")
      (value "MSS1048-153MLB")
      (footprint "eagle-import:MSS1048")
      (libsource (lib "eagle-import") (part "INDUCTOR-MSS1048"))
    )
    (comp (ref "LED1")
      (value "Green")
      (footprint "eagle-import:LED_CHIPLED_0603")
      (libsource (lib "eagle-import") (part "LED-0603"))
    )
    (comp (ref "R13")
      (value "10K")
      (footprint "eagle-import:R0603")
      (libsource (lib "eagle-import") (part "RESISTOR-0603"))
    )
    (comp (ref "R14")
      (value "133K 1%")
      (footprint "eagle-import:R0603")
      (libsource (lib "eagle-import") (part "RESISTOR-0603"))
    )
    (comp (ref "R15")
      (value "0.075 1%")
      (footprint "eagle-import:R1210")
      (libsource (lib "eagle-import") (part "RESISTOR-1210"))
    )
    (comp (ref "R16")
      (value "9.76K 1%")
      (footprint "eagle-import:R0603")
      (libsource (lib "eagle-import") (part "RESISTOR-0603"))
    )
    (comp (ref "R17")
      (value "10.0K 1%")
      (footprint "eagle-import:R0603")
      (libsource (lib "eagle-import") (part "RESISTOR-0603"))
    )
    (comp (ref "R18")
      (value "1K")
      (footprint "eagle-import:R0603")
      (libsource (lib "eagle-import") (part "RESISTOR-0603"))
    )
    (comp (ref "U4")
      (value "LM25011")
      (footprint "eagle-import:VSSOP-10")
      (libsource (lib "eagle-import") (part "LM25011"))
    )
    (comp (ref "U5")
      (value "TLV1117LV33")
      (footprint "eagle-import:SOT223")
      (libsource (lib "eagle-import") (part "AP1117SOT223"))
    )
    (comp (ref "C17")
      (value "0.1 uF")
      (footprint "eagle-import:R0603")
      (libsource (lib "eagle-import") (part "CAP0603"))
    )
    (comp (ref "C18")
      (value "0.1 uF")
      (footprint "eagle-import:R0603")
      (libsource (lib "eagle-import") (part "CAP0603"))
    )
    (comp (ref "C19")
      (value "12 pF")
      (footprint "eagle-import:R0603")
      (libsource (lib "eagle-import") (part "CAP0603"))
    )
    (comp (ref "C20")
      (value "12 pF")
      (footprint "eagle-import:R0603")
      (libsource (lib "eagle-import") (part "CAP0603"))
    )
    (comp (ref "C21")
      (value "0.1 uF")
      (footprint "eagle-import:R0603")
      (libsource (lib "eagle-import") (part "CAP0603"))
    )
    (comp (ref "C22")
      (value "0.1 uF")
      (footprint "eagle-import:R0603")
      (libsource (lib "eagle-import") (part "CAP0603"))
    )
    (comp (ref "C23")
      (value "0.1 uF")
      (footprint "eagle-import:R0603")
      (libsource (lib "eagle-import") (part "CAP0603"))
    )
    (comp (ref "LED2")
      (value "RED")
      (footprint "eagle-import:LED_CHIPLED_0603")
      (libsource (lib "eagle-import") (part "LED-0603"))
    )
    (comp (ref "LED4")
      (value "YELLOW")
      (footprint "eagle-import:LED_CHIPLED_0603")
      (libsource (lib "eagle-import") (part "LED-0603"))
    )
    (comp (ref "LED5")
      (value "RED")
      (footprint "eagle-import:LED_CHIPLED_0603")
      (libsource (lib "eagle-import") (part "LED-0603"))
    )
    (comp (ref "R19")
      (value "1K")
      (footprint "eagle-import:R0603")
      (libsource (lib "eagle-import") (part "RESISTOR-0603"))
    )
    (comp (ref "R20")
      (value "100K")
      (footprint "eagle-import:R0603")
      (libsource (lib "eagle-import") (part "RESISTOR-0603"))
    )
    (comp (ref "R22")
      (value "1K")
      (footprint "eagle-import:R0603")
      (libsource (lib "eagle-import") (part "RESISTOR-0603"))
    )
    (comp (ref "R23")
      (value "1K")
      (footprint "eagle-import:R0603")
      (libsource (lib "eagle-import") (part "RESISTOR-0603"))
    )
    (comp (ref "U6")
      (value "ATMEGA2560-16AU")
      (footprint "eagle-import:SMARTPRJ_TQFP100")
      (libsource (lib "eagle-import") (part "SMARTPRJ_ATMEGA2560AU2560-16"))
    )
    (comp (ref "X1")
      (value "16 MHz")
      (footprint "eagle-import:DISCRETE_2P-SMD-5X3.2")
      (libsource (lib "eagle-import") (part "CRYSTAL-53.2"))
    )
  )
  (nets
    (net (code "1") (name "+3V3") (class "Default")
      (node (ref "C16") (pin "1") (pinfunction "1_1") (pintype "passive"))
      (node (ref "J1") (pin "9") (pinfunction "1_9") (pintype "passive"))
      (node (ref "J4") (pin "13") (pinfunction "1_13") (pintype "passive"))
      (node (ref "J5") (pin "14") (pinfunction "14_14") (pintype "passive"))
      (node (ref "J9") (pin "2") (pinfunction "S_2") (pintype "passive"))
      (node (ref "Q8") (pin "1") (pinfunction "G_1") (pintype "passive"))
      (node (ref "Q9") (pin "1") (pinfunction "G_1") (pintype "passive"))
      (node (ref "R24") (pin "1") (pinfunction "1_1") (pintype "passive"))
      (node (ref "R27") (pin "1") (pinfunction "1_1") (pintype "passive"))
      (node (ref "R30") (pin "1") (pinfunction "1_1") (pintype "passive"))
      (node (ref "R33") (pin "1") (pinfunction "1_1") (pintype "passive"))
      (node (ref "R57") (pin "2") (pinfunction "2_2") (pintype "passive"))
      (node (ref "R58") (pin "2") (pinfunction "2_2") (pintype "passive"))
      (node (ref "U5") (pin "2") (pinfunction "VOUT_2") (pintype "power_in"))
      (node (ref "U5") (pin "4") (pinfunction "VOUT_4") (pintype "power_in"))
    )
    (net (code "2") (name "+5V") (class "Default")
      (node (ref "C13") (pin "1") (pinfunction "1_1") (pintype "passive"))
      (node (ref "C14") (pin "1") (pinfunction "1_1") (pintype "passive"))
      (node (ref "C15") (pin "1") (pinfunction "1_1") (pintype "passive"))
      (node (ref "C17") (pin "1") (pinfunction "1_1") (pintype "passive"))
      (node (ref "C18") (pin "1") (pinfunction "1_1") (pintype "passive"))
      (node (ref "C22") (pin "1") (pinfunction "1_1") (pintype "passive"))
      (node (ref "C23") (pin "1") (pinfunction "1_1") (pintype "passive"))
      (node (ref "C24") (pin "1") (pinfunction "1_1") (pintype "passive"))
      (node (ref "C25") (pin "1") (pinfunction "1_1") (pintype "passive"))
      (node (ref "C3") (pin "1") (pinfunction "1_1") (pintype "passive"))
      (node (ref "C30") (pin "1") (pinfunction "1_1") (pintype "passive"))
      (node (ref "C31") (pin "1") (pinfunction "1_1") (pintype "passive"))
      (node (ref "C32") (pin "1") (pinfunction "1_1") (pintype "passive"))
      (node (ref "C33") (pin "1") (pinfunction "1_1") (pintype "passive"))
      (node (ref "C34") (pin "+") (pinfunction "+_+") (pintype "passive"))
      (node (ref "C4") (pin "1") (pinfunction "1_1") (pintype "passive"))
      (node (ref "C7") (pin "1") (pinfunction "1_1") (pintype "passive"))
      (node (ref "J1") (pin "10") (pinfunction "1_10") (pintype "passive"))
      (node (ref "J13") (pin "2") (pinfunction "2_2") (pintype "passive"))
      (node (ref "J2") (pin "1") (pinfunction "1_1") (pintype "passive"))
      (node (ref "J2") (pin "15") (pinfunction "1_15") (pintype "passive"))
      (node (ref "J3") (pin "1") (pinfunction "1_1") (pintype "passive"))
      (node (ref "J3") (pin "15") (pinfunction "1_15") (pintype "passive"))
      (node (ref "J4") (pin "15") (pinfunction "1_15") (pintype "passive"))
      (node (ref "J6") (pin "5") (pinfunction "1_5") (pintype "passive"))
      (node (ref "J6") (pin "6") (pinfunction "1_6") (pintype "passive"))
      (node (ref "L1") (pin "P$2") (pinfunction "2_P$2") (pintype "passive"))
      (node (ref "LED4") (pin "A") (pinfunction "A_A") (pintype "passive"))
      (node (ref "R13") (pin "2") (pinfunction "2_2") (pintype "passive"))
      (node (ref "R16") (pin "2") (pinfunction "2_2") (pintype "passive"))
      (node (ref "R18") (pin "1") (pinfunction "1_1") (pintype "passive"))
      (node (ref "R20") (pin "1") (pinfunction "1_1") (pintype "passive"))
      (node (ref "R25") (pin "1") (pinfunction "1_1") (pintype "passive"))
      (node (ref "R28") (pin "1") (pinfunction "1_1") (pintype "passive"))
      (node (ref "R31") (pin "1") (pinfunction "1_1") (pintype "passive"))
      (node (ref "R34") (pin "1") (pinfunction "1_1") (pintype "passive"))
      (node (ref "R55") (pin "2") (pinfunction "2_2") (pintype "passive"))
      (node (ref "R56") (pin "2") (pinfunction "2_2") (pintype "passive"))
      (node (ref "SENS1") (pin "3") (pinfunction "V+_3") (pintype "power_in"))
      (node (ref "SENS2") (pin "1") (pinfunction "VDD_1") (pintype "power_in"))
      (node (ref "U1") (pin "3") (pinfunction "V+_3") (pintype "power_in"))
      (node (ref "U10") (pin "3") (pinfunction "V+_3") (pintype "power_in"))
      (node (ref "U11") (pin "3") (pinfunction "V+_3") (pintype "power_in"))
      (node (ref "U2") (pin "3") (pinfunction "V+_3") (pintype "power_in"))
      (node (ref "U3") (pin "3") (pinfunction "V+_3") (pintype "power_in"))
      (node (ref "U5") (pin "3") (pinfunction "VIN_3") (pintype "input"))
      (node (ref "U6") (pin "10") (pinfunction "VCC_10") (pintype "power_in"))
      (node (ref "U6") (pin "100") (pinfunction "AVCC_100") (pintype "power_in"))
      (node (ref "U6") (pin "31") (pinfunction "VCC1_31") (pintype "power_in"))
      (node (ref "U6") (pin "61") (pinfunction "VCC2_61") (pintype "power_in"))
      (node (ref "U6") (pin "80") (pinfunction "VCC3_80") (pintype "power_in"))
      (node (ref "U7") (pin "19") (pinfunction "VCCB_19") (pintype "bidirectional"))
      (node (ref "U9") (pin "3") (pinfunction "V+_3") (pintype "power_in"))
    )
    (net (code "3") (name "3V3_SCL") (class "Default")
      (node (ref "J1") (pin "11") (pinfunction "1_11") (pintype "passive"))
      (node (ref "J5") (pin "15") (pinfunction "15_15") (pintype "passive"))
      (node (ref "Q8") (pin "2") (pinfunction "S_2") (pintype "passive"))
      (node (ref "R57") (pin "1") (pinfunction "1_1") (pintype "passive"))
    )
    (net (code "4") (name "3V3_SDA") (class "Default")
      (node (ref "J1") (pin "13") (pinfunction "1_13") (pintype "passive"))
      (node (ref "J5") (pin "16") (pinfunction "16_16") (pintype "passive"))
      (node (ref "Q9") (pin "2") (pinfunction "S_2") (pintype "passive"))
      (node (ref "R58") (pin "1") (pinfunction "1_1") (pintype "passive"))
    )
    (net (code "5") (name "ADC0") (class "Default")
      (node (ref "U3") (pin "6") (pinfunction "VOUT_6") (pintype "output"))
      (node (ref "U6") (pin "97") (pinfunction "(ADC0)PF0_97") (pintype "bidirectional"))
    )
    (net (code "6") (name "ADC1") (class "Default")
      (node (ref "U11") (pin "6") (pinfunction "VOUT_6") (pintype "output"))
      (node (ref "U6") (pin "96") (pinfunction "(ADC1)PF1_96") (pintype "bidirectional"))
    )
    (net (code "7") (name "ADC2") (class "Default")
      (node (ref "U10") (pin "6") (pinfunction "VOUT_6") (pintype "output"))
      (node (ref "U6") (pin "95") (pinfunction "(ADC2)PF2_95") (pintype "bidirectional"))
    )
    (net (code "8") (name "ADC3") (class "Default")
      (node (ref "U6") (pin "94") (pinfunction "(ADC3)PF3_94") (pintype "bidirectional"))
      (node (ref "U9") (pin "6") (pinfunction "VOUT_6") (pintype "output"))
    )
    (net (code "9") (name "ADC4") (class "Default")
      (node (ref "C6") (pin "1") (pinfunction "1_1") (pintype "passive"))
      (node (ref "R10") (pin "2") (pinfunction "2_2") (pintype "passive"))
      (node (ref "R11") (pin "1") (pinfunction "1_1") (pintype "passive"))
      (node (ref "U6") (pin "93") (pinfunction "(ADC4/TCK)PF4_93") (pintype "bidirectional"))
    )
    (net (code "10") (name "ADC5") (class "Default")
      (node (ref "U1") (pin "6") (pinfunction "VOUT_6") (pintype "output"))
      (node (ref "U6") (pin "92") (pinfunction "(ADC5/TMS)PF5_92") (pintype "bidirectional"))
    )
    (net (code "11") (name "ADC6") (class "Default")
      (node (ref "U2") (pin "6") (pinfunction "VOUT_6") (pintype "output"))
      (node (ref "U6") (pin "91") (pinfunction "(ADC6/TDO)PF6_91") (pintype "bidirectional"))
    )
    (net (code "12") (name "ADC7") (class "Default")
      (node (ref "C27") (pin "1") (pinfunction "1_1") (pintype "passive"))
      (node (ref "R45") (pin "2") (pinfunction "2_2") (pintype "passive"))
      (node (ref "U6") (pin "90") (pinfunction "(ADC7/TDI)PF7_90") (pintype "bidirectional"))
    )
    (net (code "13") (name "ADC8") (class "Default")
      (node (ref "C26") (pin "1") (pinfunction "1_1") (pintype "passive"))
      (node (ref "R44") (pin "2") (pinfunction "2_2") (pintype "passive"))
      (node (ref "U6") (pin "89") (pinfunction "PK0(ADC8/PCINT16)_89") (pintype "bidirectional"))
    )
    (net (code "14") (name "ADC9") (class "Default")
      (node (ref "J4") (pin "14") (pinfunction "1_14") (pintype "passive"))
      (node (ref "U6") (pin "88") (pinfunction "PK1(ADC9/PCINT17)_88") (pintype "bidirectional"))
    )
    (net (code "15") (name "ADC10") (class "Default")
      (node (ref "J4") (pin "12") (pinfunction "1_12") (pintype "passive"))
      (node (ref "U6") (pin "87") (pinfunction "PK2(ADC10/PCINT18)_87") (pintype "bidirectional"))
    )
    (net (code "16") (name "ADC11") (class "Default")
      (node (ref "J4") (pin "10") (pinfunction "1_10") (pintype "passive"))
      (node (ref "U6") (pin "86") (pinfunction "PK3(ADC11/PCINT19)_86") (pintype "bidirectional"))
    )
    (net (code "17") (name "ADC12") (class "Default")
      (node (ref "J4") (pin "8") (pinfunction "1_8") (pintype "passive"))
      (node (ref "U6") (pin "85") (pinfunction "PK4(ADC12/PCINT20)_85") (pintype "bidirectional"))
    )
    (net (code "18") (name "ADC13") (class "Default")
      (node (ref "J4") (pin "6") (pinfunction "1_6") (pintype "passive"))
      (node (ref "U6") (pin "84") (pinfunction "PK5(ADC13/PCINT21)_84") (pintype "bidirectional"))
    )
    (net (code "19") (name "ADC14") (class "Default")
      (node (ref "J4") (pin "4") (pinfunction "1_4") (pintype "passive"))
      (node (ref "U6") (pin "83") (pinfunction "PK6(ADC14/PCINT22)_83") (pintype "bidirectional"))
    )
    (net (code "20") (name "ADC15") (class "Default")
      (node (ref "J4") (pin "2") (pinfunction "1_2") (pintype "passive"))
      (node (ref "U6") (pin "82") (pinfunction "PK7(ADC15/PCINT23)_82") (pintype "bidirectional"))
    )
    (net (code "21") (name "AREF") (class "Default")
      (node (ref "C21") (pin "1") (pinfunction "1_1") (pintype "passive"))
      (node (ref "J4") (pin "16") (pinfunction "1_16") (pintype "passive"))
      (node (ref "U6") (pin "98") (pinfunction "AREF_98") (pintype "bidirectional"))
    )
    (net (code "22") (name "BAT_1+") (class "Default")
      (node (ref "C1") (pin "1") (pinfunction "1_1") (pintype "passive"))
      (node (ref "D1") (pin "1") (pinfunction "A_1") (pintype "passive"))
      (node (ref "D1") (pin "3") (pinfunction "A_3") (pintype "passive"))
      (node (ref "J5") (pin "5") (pinfunction "5_5") (pintype "passive"))
    )
    (net (code "23") (name "BAT_2+") (class "Default")
      (node (ref "C2") (pin "1") (pinfunction "1_1") (pintype "passive"))
      (node (ref "D2") (pin "1") (pinfunction "A_1") (pintype "passive"))
      (node (ref "D2") (pin "3") (pinfunction "A_3") (pintype "passive"))
      (node (ref "J5") (pin "6") (pinfunction "6_6") (pintype "passive"))
    )
    (net (code "24") (name "BB_3V3") (class "Default")
      (node (ref "C28") (pin "1") (pinfunction "1_1") (pintype "passive"))
      (node (ref "C29") (pin "1") (pinfunction "1_1") (pintype "passive"))
      (node (ref "J6") (pin "3") (pinfunction "1_3") (pintype "passive"))
      (node (ref "J6") (pin "4") (pinfunction "1_4") (pintype "passive"))
      (node (ref "LED3") (pin "A") (pinfunction "A_A") (pintype "passive"))
      (node (ref "R46") (pin "2") (pinfunction "2_2") (pintype "passive"))
      (node (ref "R47") (pin "2") (pinfunction "2_2") (pintype "passive"))
      (node (ref "R49") (pin "2") (pinfunction "2_2") (pintype "passive"))
      (node (ref "R50") (pin "2") (pinfunction "2_2") (pintype "passive"))
      (node (ref "R51") (pin "2") (pinfunction "2_2") (pintype "passive"))
      (node (ref "R52") (pin "2") (pinfunction "2_2") (pintype "passive"))
      (node (ref "R53") (pin "2") (pinfunction "2_2") (pintype "passive"))
      (node (ref "R54") (pin "2") (pinfunction "2_2") (pintype "passive"))
      (node (ref "R62") (pin "2") (pinfunction "2_2") (pintype "passive"))
      (node (ref "U7") (pin "2") (pinfunction "VCCA_2") (pintype "bidirectional"))
      (node (ref "U8") (pin "8") (pinfunction "VCC_8") (pintype "bidirectional"))
    )
    (net (code "25") (name "BB_P9_11") (class "Default")
      (node (ref "J6") (pin "11") (pinfunction "1_11") (pintype "passive"))
      (node (ref "R46") (pin "1") (pinfunction "1_1") (pintype "passive"))
      (node (ref "U7") (pin "8") (pinfunction "A7_8") (pintype "bidirectional"))
    )
    (net (code "26") (name "BB_P9_12") (class "Default")
      (node (ref "J6") (pin "12") (pinfunction "1_12") (pintype "passive"))
    )
    (net (code "27") (name "BB_P9_13") (class "Default")
      (node (ref "J6") (pin "13") (pinfunction "1_13") (pintype "passive"))
    )
    (net (code "28") (name "BB_P9_14") (class "Default")
      (node (ref "J6") (pin "14") (pinfunction "1_14") (pintype "passive"))
    )
    (net (code "29") (name "BB_P9_15") (class "Default")
      (node (ref "J6") (pin "15") (pinfunction "1_15") (pintype "passive"))
    )
    (net (code "30") (name "BB_P9_16") (class "Default")
      (node (ref "J6") (pin "16") (pinfunction "1_16") (pintype "passive"))
    )
    (net (code "31") (name "BB_P9_17") (class "Default")
      (node (ref "J6") (pin "17") (pinfunction "1_17") (pintype "passive"))
      (node (ref "U7") (pin "4") (pinfunction "A3_4") (pintype "bidirectional"))
    )
    (net (code "32") (name "BB_P9_18") (class "Default")
      (node (ref "J6") (pin "18") (pinfunction "1_18") (pintype "passive"))
      (node (ref "U7") (pin "6") (pinfunction "A5_6") (pintype "bidirectional"))
    )
    (net (code "33") (name "BB_P9_19") (class "Default")
      (node (ref "J6") (pin "19") (pinfunction "1_19") (pintype "passive"))
      (node (ref "R53") (pin "1") (pinfunction "1_1") (pintype "passive"))
      (node (ref "U8") (pin "6") (pinfunction "SCL_6") (pintype "bidirectional"))
    )
    (net (code "34") (name "BB_P9_20") (class "Default")
      (node (ref "J6") (pin "20") (pinfunction "1_20") (pintype "passive"))
      (node (ref "R54") (pin "1") (pinfunction "1_1") (pintype "passive"))
      (node (ref "U8") (pin "5") (pinfunction "SDA_5") (pintype "bidirectional"))
    )
    (net (code "35") (name "BB_P9_21") (class "Default")
      (node (ref "J6") (pin "21") (pinfunction "1_21") (pintype "passive"))
      (node (ref "U7") (pin "7") (pinfunction "A6_7") (pintype "bidirectional"))
    )
    (net (code "36") (name "BB_P9_22") (class "Default")
      (node (ref "J6") (pin "22") (pinfunction "1_22") (pintype "passive"))
      (node (ref "U7") (pin "5") (pinfunction "A4_5") (pintype "bidirectional"))
    )
    (net (code "37") (name "BB_P9_23") (class "Default")
      (node (ref "J6") (pin "23") (pinfunction "1_23") (pintype "passive"))
    )
    (net (code "38") (name "BB_P9_24") (class "Default")
      (node (ref "J6") (pin "24") (pinfunction "1_24") (pintype "passive"))
      (node (ref "R21") (pin "2") (pinfunction "2_2") (pintype "passive"))
      (node (ref "U7") (pin "1") (pinfunction "A1_1") (pintype "bidirectional"))
    )
    (net (code "39") (name "BB_P9_25") (class "Default")
      (node (ref "J6") (pin "25") (pinfunction "1_25") (pintype "passive"))
    )
    (net (code "40") (name "BB_P9_26") (class "Default")
      (node (ref "J6") (pin "26") (pinfunction "1_26") (pintype "passive"))
      (node (ref "U7") (pin "3") (pinfunction "A2_3") (pintype "bidirectional"))
    )
    (net (code "41") (name "BB_P9_27") (class "Default")
      (node (ref "J6") (pin "27") (pinfunction "1_27") (pintype "passive"))
    )
    (net (code "42") (name "BB_P9_28") (class "Default")
      (node (ref "J6") (pin "28") (pinfunction "1_28") (pintype "passive"))
    )
    (net (code "43") (name "BB_P9_29") (class "Default")
      (node (ref "J6") (pin "29") (pinfunction "1_29") (pintype "passive"))
    )
    (net (code "44") (name "BB_P9_30") (class "Default")
      (node (ref "J6") (pin "30") (pinfunction "1_30") (pintype "passive"))
    )
    (net (code "45") (name "BB_P9_31") (class "Default")
      (node (ref "J6") (pin "31") (pinfunction "1_31") (pintype "passive"))
    )
    (net (code "46") (name "BB_P9_32") (class "Default")
      (node (ref "J6") (pin "32") (pinfunction "1_32") (pintype "passive"))
    )
    (net (code "47") (name "BB_P9_33") (class "Default")
      (node (ref "J6") (pin "33") (pinfunction "1_33") (pintype "passive"))
    )
    (net (code "48") (name "BB_P9_34") (class "Default")
      (node (ref "J6") (pin "34") (pinfunction "1_34") (pintype "passive"))
    )
    (net (code "49") (name "BB_P9_35") (class "Default")
      (node (ref "J6") (pin "35") (pinfunction "1_35") (pintype "passive"))
    )
    (net (code "50") (name "BB_P9_36") (class "Default")
      (node (ref "J6") (pin "36") (pinfunction "1_36") (pintype "passive"))
    )
    (net (code "51") (name "BB_P9_37") (class "Default")
      (node (ref "J6") (pin "37") (pinfunction "1_37") (pintype "passive"))
    )
    (net (code "52") (name "BB_P9_38") (class "Default")
      (node (ref "J6") (pin "38") (pinfunction "1_38") (pintype "passive"))
    )
    (net (code "53") (name "BB_P9_39") (class "Default")
      (node (ref "J6") (pin "39") (pinfunction "1_39") (pintype "passive"))
    )
    (net (code "54") (name "BB_P9_40") (class "Default")
      (node (ref "J6") (pin "40") (pinfunction "1_40") (pintype "passive"))
    )
    (net (code "55") (name "BB_P9_41") (class "Default")
      (node (ref "J6") (pin "41") (pinfunction "1_41") (pintype "passive"))
    )
    (net (code "56") (name "BB_P9_42") (class "Default")
      (node (ref "J6") (pin "42") (pinfunction "1_42") (pintype "passive"))
    )
    (net (code "57") (name "BB_PWR_BUT") (class "Default")
      (node (ref "J6") (pin "9") (pinfunction "1_9") (pintype "passive"))
    )
    (net (code "58") (name "BB_SYS_5V") (class "Default")
      (node (ref "J6") (pin "7") (pinfunction "1_7") (pintype "passive"))
      (node (ref "J6") (pin "8") (pinfunction "1_8") (pintype "passive"))
    )
    (net (code "59") (name "BB_SYS_RESET*") (class "Default")
      (node (ref "J6") (pin "10") (pinfunction "1_10") (pintype "passive"))
      (node (ref "R48") (pin "2") (pinfunction "2_2") (pintype "passive"))
    )
    (net (code "60") (name "D0{slash}UART_RX") (class "Default")
      (node (ref "U6") (pin "2") (pinfunction "(RXD0/PCIN8)PE0_2") (pintype "bidirectional"))
      (node (ref "U7") (pin "20") (pinfunction "B1_20") (pintype "bidirectional"))
    )
    (net (code "61") (name "D1{slash}UART_TX") (class "Default")
      (node (ref "R22") (pin "2") (pinfunction "2_2") (pintype "passive"))
      (node (ref "U6") (pin "3") (pinfunction "(TXD0)PE1_3") (pintype "bidirectional"))
      (node (ref "U7") (pin "18") (pinfunction "B2_18") (pintype "bidirectional"))
    )
    (net (code "62") (name "D2") (class "Default")
      (node (ref "J3") (pin "11") (pinfunction "1_11") (pintype "passive"))
      (node (ref "U6") (pin "6") (pinfunction "(OC3B/INT4)PE4_6") (pintype "bidirectional"))
    )
    (net (code "63") (name "D3") (class "Default")
      (node (ref "J3") (pin "9") (pinfunction "1_9") (pintype "passive"))
      (node (ref "U6") (pin "7") (pinfunction "(OC3C/INT5)PE5_7") (pintype "bidirectional"))
    )
    (net (code "64") (name "D4") (class "Default")
      (node (ref "J3") (pin "7") (pinfunction "1_7") (pintype "passive"))
      (node (ref "U6") (pin "1") (pinfunction "(OC0B)PG5_1") (pintype "bidirectional"))
    )
    (net (code "65") (name "D5") (class "Default")
      (node (ref "J3") (pin "5") (pinfunction "1_5") (pintype "passive"))
      (node (ref "U6") (pin "5") (pinfunction "(OC3A/AIN1)PE3_5") (pintype "bidirectional"))
    )
    (net (code "66") (name "D6") (class "Default")
      (node (ref "J8") (pin "P1") (pinfunction "1_P1") (pintype "passive"))
      (node (ref "U6") (pin "15") (pinfunction "PH3(OC4A)_15") (pintype "bidirectional"))
    )
    (net (code "67") (name "D7") (class "Default")
      (node (ref "J8") (pin "P4") (pinfunction "1_P4") (pintype "passive"))
      (node (ref "U6") (pin "16") (pinfunction "PH4(OC4B)_16") (pintype "bidirectional"))
    )
    (net (code "68") (name "D8") (class "Default")
      (node (ref "J8") (pin "P7") (pinfunction "1_P7") (pintype "passive"))
      (node (ref "U6") (pin "17") (pinfunction "PH5(OC4C)_17") (pintype "bidirectional"))
    )
    (net (code "69") (name "D9") (class "Default")
      (node (ref "J8") (pin "P10") (pinfunction "1_P10") (pintype "passive"))
      (node (ref "U6") (pin "18") (pinfunction "PH6(OC2B)_18") (pintype "bidirectional"))
    )
    (net (code "70") (name "D10") (class "Default")
      (node (ref "J8") (pin "P13") (pinfunction "1_P13") (pintype "passive"))
      (node (ref "U6") (pin "23") (pinfunction "(OC2A/PCINT4)PB4_23") (pintype "bidirectional"))
    )
    (net (code "71") (name "D11") (class "Default")
      (node (ref "J8") (pin "P16") (pinfunction "1_P16") (pintype "passive"))
      (node (ref "U6") (pin "24") (pinfunction "(OC1A/PCINT5)PB5_24") (pintype "bidirectional"))
    )
    (net (code "72") (name "D12") (class "Default")
      (node (ref "R39") (pin "1") (pinfunction "1_1") (pintype "passive"))
      (node (ref "U6") (pin "25") (pinfunction "(OC1B/PCINT6)PB6_25") (pintype "bidirectional"))
    )
    (net (code "73") (name "D13") (class "Default")
      (node (ref "R23") (pin "1") (pinfunction "1_1") (pintype "passive"))
      (node (ref "U6") (pin "26") (pinfunction "(OC0A/OC1C/PCINT7)PB7_26") (pintype "bidirectional"))
    )
    (net (code "74") (name "D14") (class "Default")
      (node (ref "J2") (pin "11") (pinfunction "1_11") (pintype "passive"))
      (node (ref "U6") (pin "64") (pinfunction "PJ1(TXD3/PCINT10)_64") (pintype "bidirectional"))
    )
    (net (code "75") (name "D15") (class "Default")
      (node (ref "J2") (pin "9") (pinfunction "1_9") (pintype "passive"))
      (node (ref "U6") (pin "63") (pinfunction "PJ0(RXD3/PCINT9)_63") (pintype "bidirectional"))
    )
    (net (code "76") (name "D16{slash}ESC_POWER_SWITCH") (class "Default")
      (node (ref "R5") (pin "2") (pinfunction "2_2") (pintype "passive"))
      (node (ref "U6") (pin "13") (pinfunction "PH1(TXD2)_13") (pintype "bidirectional"))
    )
    (net (code "77") (name "D17") (class "Default")
      (node (ref "U6") (pin "12") (pinfunction "PH0(RXD2)_12") (pintype "bidirectional"))
    )
    (net (code "78") (name "D18") (class "Default")
      (node (ref "J2") (pin "7") (pinfunction "1_7") (pintype "passive"))
      (node (ref "U6") (pin "46") (pinfunction "(TXD1/INT3)PD3_46") (pintype "bidirectional"))
    )
    (net (code "79") (name "D19") (class "Default")
      (node (ref "J2") (pin "5") (pinfunction "1_5") (pintype "passive"))
      (node (ref "U6") (pin "45") (pinfunction "(RXD1/INT2)PD2_45") (pintype "bidirectional"))
    )
    (net (code "80") (name "D20{slash}5V_SDA") (class "Default")
      (node (ref "J1") (pin "14") (pinfunction "1_14") (pintype "passive"))
      (node (ref "Q9") (pin "3") (pinfunction "D_3") (pintype "passive"))
      (node (ref "R56") (pin "1") (pinfunction "1_1") (pintype "passive"))
      (node (ref "U6") (pin "44") (pinfunction "(SDA/INT1)PD1_44") (pintype "bidirectional"))
    )
    (net (code "81") (name "D21{slash}5V_SCL") (class "Default")
      (node (ref "J1") (pin "12") (pinfunction "1_12") (pintype "passive"))
      (node (ref "Q8") (pin "3") (pinfunction "D_3") (pintype "passive"))
      (node (ref "R55") (pin "1") (pinfunction "1_1") (pintype "passive"))
      (node (ref "U6") (pin "43") (pinfunction "(SCL/INT0)PD0_43") (pintype "bidirectional"))
    )
    (net (code "82") (name "D22") (class "Default")
      (node (ref "J3") (pin "16") (pinfunction "1_16") (pintype "passive"))
      (node (ref "U6") (pin "78") (pinfunction "(AD0)PA0_78") (pintype "bidirectional"))
    )
    (net (code "83") (name "D23") (class "Default")
      (node (ref "J3") (pin "14") (pinfunction "1_14") (pintype "passive"))
      (node (ref "U6") (pin "77") (pinfunction "(AD1)PA1_77") (pintype "bidirectional"))
    )
    (net (code "84") (name "D24") (class "Default")
      (node (ref "J3") (pin "12") (pinfunction "1_12") (pintype "passive"))
      (node (ref "U6") (pin "76") (pinfunction "(AD2)PA2_76") (pintype "bidirectional"))
    )
    (net (code "85") (name "D25") (class "Default")
      (node (ref "J3") (pin "10") (pinfunction "1_10") (pintype "passive"))
      (node (ref "U6") (pin "75") (pinfunction "(AD3)PA3_75") (pintype "bidirectional"))
    )
    (net (code "86") (name "D26") (class "Default")
      (node (ref "J3") (pin "8") (pinfunction "1_8") (pintype "passive"))
      (node (ref "U6") (pin "74") (pinfunction "(AD4)PA4_74") (pintype "bidirectional"))
    )
    (net (code "87") (name "D27") (class "Default")
      (node (ref "J3") (pin "6") (pinfunction "1_6") (pintype "passive"))
      (node (ref "U6") (pin "73") (pinfunction "(AD5)PA5_73") (pintype "bidirectional"))
    )
    (net (code "88") (name "D28") (class "Default")
      (node (ref "J3") (pin "4") (pinfunction "1_4") (pintype "passive"))
      (node (ref "U6") (pin "72") (pinfunction "(AD6)PA6_72") (pintype "bidirectional"))
    )
    (net (code "89") (name "D29") (class "Default")
      (node (ref "J3") (pin "2") (pinfunction "1_2") (pintype "passive"))
      (node (ref "U6") (pin "71") (pinfunction "(AD7)PA7_71") (pintype "bidirectional"))
    )
    (net (code "90") (name "D30") (class "Default")
      (node (ref "J2") (pin "16") (pinfunction "1_16") (pintype "passive"))
      (node (ref "U6") (pin "60") (pinfunction "(A15)PC7_60") (pintype "bidirectional"))
    )
    (net (code "91") (name "D31") (class "Default")
      (node (ref "J2") (pin "14") (pinfunction "1_14") (pintype "passive"))
      (node (ref "U6") (pin "59") (pinfunction "(A14)PC6_59") (pintype "bidirectional"))
    )
    (net (code "92") (name "D32") (class "Default")
      (node (ref "J2") (pin "12") (pinfunction "1_12") (pintype "passive"))
      (node (ref "U6") (pin "58") (pinfunction "(A13)PC5_58") (pintype "bidirectional"))
    )
    (net (code "93") (name "D33") (class "Default")
      (node (ref "J2") (pin "10") (pinfunction "1_10") (pintype "passive"))
      (node (ref "U6") (pin "57") (pinfunction "(A12)PC4_57") (pintype "bidirectional"))
    )
    (net (code "94") (name "D34") (class "Default")
      (node (ref "J2") (pin "8") (pinfunction "1_8") (pintype "passive"))
      (node (ref "U6") (pin "56") (pinfunction "(A11)PC3_56") (pintype "bidirectional"))
    )
    (net (code "95") (name "D35") (class "Default")
      (node (ref "J2") (pin "6") (pinfunction "1_6") (pintype "passive"))
      (node (ref "U6") (pin "55") (pinfunction "(A10)PC2_55") (pintype "bidirectional"))
    )
    (net (code "96") (name "D36") (class "Default")
      (node (ref "J2") (pin "4") (pinfunction "1_4") (pintype "passive"))
      (node (ref "U6") (pin "54") (pinfunction "(A9)PC1_54") (pintype "bidirectional"))
    )
    (net (code "97") (name "D37") (class "Default")
      (node (ref "J2") (pin "2") (pinfunction "1_2") (pintype "passive"))
      (node (ref "U6") (pin "53") (pinfunction "(A8)PC0_53") (pintype "bidirectional"))
    )
    (net (code "98") (name "D38") (class "Default")
      (node (ref "U6") (pin "50") (pinfunction "(T0)PD7_50") (pintype "bidirectional"))
    )
    (net (code "99") (name "D39") (class "Default")
      (node (ref "U6") (pin "70") (pinfunction "(ALE)PG2_70") (pintype "bidirectional"))
    )
    (net (code "100") (name "D40") (class "Default")
      (node (ref "U6") (pin "52") (pinfunction "(RD)PG1_52") (pintype "bidirectional"))
    )
    (net (code "101") (name "D41") (class "Default")
      (node (ref "U6") (pin "51") (pinfunction "(WR)PG0_51") (pintype "bidirectional"))
    )
    (net (code "102") (name "D42") (class "Default")
      (node (ref "U6") (pin "42") (pinfunction "PL7_42") (pintype "bidirectional"))
    )
    (net (code "103") (name "D43") (class "Default")
      (node (ref "U6") (pin "41") (pinfunction "PL6_41") (pintype "bidirectional"))
    )
    (net (code "104") (name "D44") (class "Default")
      (node (ref "R36") (pin "1") (pinfunction "1_1") (pintype "passive"))
      (node (ref "U6") (pin "40") (pinfunction "PL5(OC5C)_40") (pintype "bidirectional"))
    )
    (net (code "105") (name "D45") (class "Default")
      (node (ref "R37") (pin "1") (pinfunction "1_1") (pintype "passive"))
      (node (ref "U6") (pin "39") (pinfunction "PL4(OC5B)_39") (pintype "bidirectional"))
    )
    (net (code "106") (name "D46") (class "Default")
      (node (ref "R38") (pin "1") (pinfunction "1_1") (pintype "passive"))
      (node (ref "U6") (pin "38") (pinfunction "PL3(OC5A)_38") (pintype "bidirectional"))
    )
    (net (code "107") (name "D47") (class "Default")
      (node (ref "U6") (pin "37") (pinfunction "PL2(T5)_37") (pintype "bidirectional"))
    )
    (net (code "108") (name "D48") (class "Default")
      (node (ref "U6") (pin "36") (pinfunction "PL1(ICP5)_36") (pintype "bidirectional"))
    )
    (net (code "109") (name "D49") (class "Default")
      (node (ref "R19") (pin "1") (pinfunction "1_1") (pintype "passive"))
      (node (ref "U6") (pin "35") (pinfunction "PL0(ICP4)_35") (pintype "bidirectional"))
    )
    (net (code "110") (name "D50{slash}SPI_MISO") (class "Default")
      (node (ref "J13") (pin "1") (pinfunction "1_1") (pintype "passive"))
      (node (ref "U6") (pin "22") (pinfunction "(MISO/PCINT3)PB3_22") (pintype "bidirectional"))
      (node (ref "U7") (pin "14") (pinfunction "B6_14") (pintype "bidirectional"))
    )
    (net (code "111") (name "D51{slash}SPI_MOSI") (class "Default")
      (node (ref "J13") (pin "4") (pinfunction "4_4") (pintype "passive"))
      (node (ref "U6") (pin "21") (pinfunction "(MOSI/PCINT2)PB2_21") (pintype "bidirectional"))
      (node (ref "U7") (pin "15") (pinfunction "B5_15") (pintype "bidirectional"))
    )
    (net (code "112") (name "D52{slash}SPI_SCK") (class "Default")
      (node (ref "J13") (pin "3") (pinfunction "3_3") (pintype "passive"))
      (node (ref "U6") (pin "20") (pinfunction "(SCK/PCINT1)PB1_20") (pintype "bidirectional"))
      (node (ref "U7") (pin "16") (pinfunction "B4_16") (pintype "bidirectional"))
    )
    (net (code "113") (name "D53{slash}SPI_SS") (class "Default")
      (node (ref "U6") (pin "19") (pinfunction "(SS/PCINT0)PB0_19") (pintype "bidirectional"))
      (node (ref "U7") (pin "17") (pinfunction "B3_17") (pintype "bidirectional"))
    )
    (net (code "114") (name "ESC_1A") (class "Default")
      (node (ref "J14") (pin "2") (pinfunction "S_2") (pintype "passive"))
      (node (ref "J5") (pin "1") (pinfunction "1_1") (pintype "passive"))
    )
    (net (code "115") (name "ESC_1B") (class "Default")
      (node (ref "J14") (pin "3") (pinfunction "S_3") (pintype "passive"))
      (node (ref "J5") (pin "2") (pinfunction "2_2") (pintype "passive"))
    )
    (net (code "116") (name "ESC_1C") (class "Default")
      (node (ref "J14") (pin "4") (pinfunction "S_4") (pintype "passive"))
      (node (ref "J5") (pin "3") (pinfunction "3_3") (pintype "passive"))
    )
    (net (code "117") (name "ESC_2A") (class "Default")
      (node (ref "J15") (pin "2") (pinfunction "S_2") (pintype "passive"))
      (node (ref "J5") (pin "8") (pinfunction "8_8") (pintype "passive"))
    )
    (net (code "118") (name "ESC_2B") (class "Default")
      (node (ref "J15") (pin "3") (pinfunction "S_3") (pintype "passive"))
      (node (ref "J5") (pin "9") (pinfunction "9_9") (pintype "passive"))
    )
    (net (code "119") (name "ESC_2C") (class "Default")
      (node (ref "J15") (pin "4") (pinfunction "S_4") (pintype "passive"))
      (node (ref "J5") (pin "10") (pinfunction "10_10") (pintype "passive"))
    )
    (net (code "120") (name "ESC_3A") (class "Default")
      (node (ref "J16") (pin "2") (pinfunction "S_2") (pintype "passive"))
      (node (ref "J5") (pin "11") (pinfunction "11_11") (pintype "passive"))
    )
    (net (code "121") (name "ESC_3B") (class "Default")
      (node (ref "J16") (pin "3") (pinfunction "S_3") (pintype "passive"))
      (node (ref "J5") (pin "12") (pinfunction "12_12") (pintype "passive"))
    )
    (net (code "122") (name "ESC_3C") (class "Default")
      (node (ref "J16") (pin "4") (pinfunction "S_4") (pintype "passive"))
      (node (ref "J5") (pin "13") (pinfunction "13_13") (pintype "passive"))
    )
    (net (code "123") (name "ESC_POWER") (class "Default")
      (node (ref "Q3") (pin "5") (pinfunction "D_5") (pintype "passive"))
      (node (ref "Q3") (pin "6") (pinfunction "D_6") (pintype "passive"))
      (node (ref "Q3") (pin "7") (pinfunction "D_7") (pintype "passive"))
      (node (ref "Q3") (pin "8") (pinfunction "D_8") (pintype "passive"))
      (node (ref "R59") (pin "1") (pinfunction "1_1") (pintype "passive"))
      (node (ref "R60") (pin "1") (pinfunction "1_1") (pintype "passive"))
      (node (ref "R61") (pin "1") (pinfunction "1_1") (pintype "passive"))
      (node (ref "U10") (pin "4") (pinfunction "IN+_4") (pintype "input"))
      (node (ref "U11") (pin "4") (pinfunction "IN+_4") (pintype "input"))
      (node (ref "U9") (pin "4") (pinfunction "IN+_4") (pintype "input"))
    )
    (net (code "124") (name "GND") (class "Default")
      (node (ref "C1") (pin "2") (pinfunction "2_2") (pintype "passive"))
      (node (ref "C10") (pin "2") (pinfunction "2_2") (pintype "passive"))
      (node (ref "C11") (pin "2") (pinfunction "2_2") (pintype "passive"))
      (node (ref "C13") (pin "2") (pinfunction "2_2") (pintype "passive"))
      (node (ref "C14") (pin "2") (pinfunction "2_2") (pintype "passive"))
      (node (ref "C15") (pin "2") (pinfunction "2_2") (pintype "passive"))
      (node (ref "C16") (pin "2") (pinfunction "2_2") (pintype "passive"))
      (node (ref "C17") (pin "2") (pinfunction "2_2") (pintype "passive"))
      (node (ref "C18") (pin "2") (pinfunction "2_2") (pintype "passive"))
      (node (ref "C19") (pin "2") (pinfunction "2_2") (pintype "passive"))
      (node (ref "C2") (pin "2") (pinfunction "2_2") (pintype "passive"))
      (node (ref "C20") (pin "2") (pinfunction "2_2") (pintype "passive"))
      (node (ref "C21") (pin "2") (pinfunction "2_2") (pintype "passive"))
      (node (ref "C22") (pin "2") (pinfunction "2_2") (pintype "passive"))
      (node (ref "C23") (pin "2") (pinfunction "2_2") (pintype "passive"))
      (node (ref "C24") (pin "2") (pinfunction "2_2") (pintype "passive"))
      (node (ref "C25") (pin "2") (pinfunction "2_2") (pintype "passive"))
      (node (ref "C26") (pin "2") (pinfunction "2_2") (pintype "passive"))
      (node (ref "C27") (pin "2") (pinfunction "2_2") (pintype "passive"))
      (node (ref "C28") (pin "2") (pinfunction "2_2") (pintype "passive"))
      (node (ref "C29") (pin "2") (pinfunction "2_2") (pintype "passive"))
      (node (ref "C3") (pin "2") (pinfunction "2_2") (pintype "passive"))
      (node (ref "C30") (pin "2") (pinfunction "2_2") (pintype "passive"))
      (node (ref "C31") (pin "2") (pinfunction "2_2") (pintype "passive"))
      (node (ref "C32") (pin "2") (pinfunction "2_2") (pintype "passive"))
      (node (ref "C33") (pin "2") (pinfunction "2_2") (pintype "passive"))
      (node (ref "C34") (pin "-") (pinfunction "-_-") (pintype "passive"))
      (node (ref "C35") (pin "2") (pinfunction "2_2") (pintype "passive"))
      (node (ref "C4") (pin "2") (pinfunction "2_2") (pintype "passive"))
      (node (ref "C6") (pin "2") (pinfunction "2_2") (pintype "passive"))
      (node (ref "C7") (pin "2") (pinfunction "2_2") (pintype "passive"))
      (node (ref "C8") (pin "2") (pinfunction "2_2") (pintype "passive"))
      (node (ref "C9") (pin "2") (pinfunction "2_2") (pintype "passive"))
      (node (ref "D3") (pin "A") (pinfunction "A_A") (pintype "passive"))
      (node (ref "J1") (pin "15") (pinfunction "1_15") (pintype "passive"))
      (node (ref "J1") (pin "16") (pinfunction "1_16") (pintype "passive"))
      (node (ref "J11") (pin "2") (pinfunction "S_2") (pintype "passive"))
      (node (ref "J12") (pin "2") (pinfunction "S_2") (pintype "passive"))
      (node (ref "J13") (pin "6") (pinfunction "6_6") (pintype "passive"))
      (node (ref "J14") (pin "5") (pinfunction "S_5") (pintype "passive"))
      (node (ref "J15") (pin "5") (pinfunction "S_5") (pintype "passive"))
      (node (ref "J16") (pin "5") (pinfunction "S_5") (pintype "passive"))
      (node (ref "J17") (pin "2") (pinfunction "S_2") (pintype "passive"))
      (node (ref "J2") (pin "13") (pinfunction "1_13") (pintype "passive"))
      (node (ref "J2") (pin "3") (pinfunction "1_3") (pintype "passive"))
      (node (ref "J3") (pin "13") (pinfunction "1_13") (pintype "passive"))
      (node (ref "J3") (pin "3") (pinfunction "1_3") (pintype "passive"))
      (node (ref "J4") (pin "1") (pinfunction "1_1") (pintype "passive"))
      (node (ref "J4") (pin "11") (pinfunction "1_11") (pintype "passive"))
      (node (ref "J4") (pin "3") (pinfunction "1_3") (pintype "passive"))
      (node (ref "J4") (pin "5") (pinfunction "1_5") (pintype "passive"))
      (node (ref "J4") (pin "7") (pinfunction "1_7") (pintype "passive"))
      (node (ref "J4") (pin "9") (pinfunction "1_9") (pintype "passive"))
      (node (ref "J5") (pin "17") (pinfunction "17_17") (pintype "passive"))
      (node (ref "J5") (pin "4") (pinfunction "4_4") (pintype "passive"))
      (node (ref "J5") (pin "7") (pinfunction "7_7") (pintype "passive"))
      (node (ref "J6") (pin "1") (pinfunction "1_1") (pintype "passive"))
      (node (ref "J6") (pin "2") (pinfunction "1_2") (pintype "passive"))
      (node (ref "J6") (pin "43") (pinfunction "1_43") (pintype "passive"))
      (node (ref "J6") (pin "44") (pinfunction "1_44") (pintype "passive"))
      (node (ref "J6") (pin "45") (pinfunction "1_45") (pintype "passive"))
      (node (ref "J6") (pin "46") (pinfunction "1_46") (pintype "passive"))
      (node (ref "J7") (pin "2") (pinfunction "S_2") (pintype "passive"))
      (node (ref "J8") (pin "P12") (pinfunction "1_P12") (pintype "passive"))
      (node (ref "J8") (pin "P15") (pinfunction "1_P15") (pintype "passive"))
      (node (ref "J8") (pin "P18") (pinfunction "1_P18") (pintype "passive"))
      (node (ref "J8") (pin "P3") (pinfunction "1_P3") (pintype "passive"))
      (node (ref "J8") (pin "P6") (pinfunction "1_P6") (pintype "passive"))
      (node (ref "J8") (pin "P9") (pinfunction "1_P9") (pintype "passive"))
      (node (ref "J9") (pin "1") (pinfunction "S_1") (pintype "passive"))
      (node (ref "J9") (pin "3") (pinfunction "S_3") (pintype "passive"))
      (node (ref "LED1") (pin "C") (pinfunction "C_C") (pintype "passive"))
      (node (ref "LED2") (pin "C") (pinfunction "C_C") (pintype "passive"))
      (node (ref "LED5") (pin "C") (pinfunction "C_C") (pintype "passive"))
      (node (ref "OC1") (pin "3") (pinfunction "E_3") (pintype "passive"))
      (node (ref "Q2") (pin "2") (pinfunction "S_2") (pintype "passive"))
      (node (ref "Q4") (pin "2") (pinfunction "S_2") (pintype "passive"))
      (node (ref "Q5") (pin "2") (pinfunction "S_2") (pintype "passive"))
      (node (ref "Q6") (pin "2") (pinfunction "S_2") (pintype "passive"))
      (node (ref "Q7") (pin "2") (pinfunction "S_2") (pintype "passive"))
      (node (ref "R11") (pin "2") (pinfunction "2_2") (pintype "passive"))
      (node (ref "R15") (pin "1") (pinfunction "1_1") (pintype "passive"))
      (node (ref "R17") (pin "1") (pinfunction "1_1") (pintype "passive"))
      (node (ref "R40") (pin "1") (pinfunction "1_1") (pintype "passive"))
      (node (ref "R41") (pin "1") (pinfunction "1_1") (pintype "passive"))
      (node (ref "R42") (pin "1") (pinfunction "1_1") (pintype "passive"))
      (node (ref "R43") (pin "1") (pinfunction "1_1") (pintype "passive"))
      (node (ref "R7") (pin "2") (pinfunction "2_2") (pintype "passive"))
      (node (ref "S1") (pin "1") (pinfunction "1_1") (pintype "passive"))
      (node (ref "S1") (pin "2") (pinfunction "2_2") (pintype "passive"))
      (node (ref "SENS1") (pin "1") (pinfunction "GND_1") (pintype "power_in"))
      (node (ref "SENS1") (pin "PAD") (pinfunction "PAD_PAD") (pintype "power_in"))
      (node (ref "SENS2") (pin "3") (pinfunction "GND_3") (pintype "power_in"))
      (node (ref "U1") (pin "1") (pinfunction "REF_1") (pintype "input"))
      (node (ref "U1") (pin "2") (pinfunction "GND_2") (pintype "power_in"))
      (node (ref "U10") (pin "1") (pinfunction "REF_1") (pintype "input"))
      (node (ref "U10") (pin "2") (pinfunction "GND_2") (pintype "power_in"))
      (node (ref "U11") (pin "1") (pinfunction "REF_1") (pintype "input"))
      (node (ref "U11") (pin "2") (pinfunction "GND_2") (pintype "power_in"))
      (node (ref "U2") (pin "1") (pinfunction "REF_1") (pintype "input"))
      (node (ref "U2") (pin "2") (pinfunction "GND_2") (pintype "power_in"))
      (node (ref "U3") (pin "1") (pinfunction "REF_1") (pintype "input"))
      (node (ref "U3") (pin "2") (pinfunction "GND_2") (pintype "power_in"))
      (node (ref "U4") (pin "11") (pinfunction "DAP_11") (pintype "bidirectional"))
      (node (ref "U4") (pin "5") (pinfunction "SGND_5") (pintype "bidirectional"))
      (node (ref "U4") (pin "7") (pinfunction "CSG_7") (pintype "bidirectional"))
      (node (ref "U5") (pin "1") (pinfunction "GND_1") (pintype "power_in"))
      (node (ref "U6") (pin "11") (pinfunction "GND_11") (pintype "power_in"))
      (node (ref "U6") (pin "32") (pinfunction "GND1_32") (pintype "power_in"))
      (node (ref "U6") (pin "62") (pinfunction "GND2_62") (pintype "power_in"))
      (node (ref "U6") (pin "81") (pinfunction "GND3_81") (pintype "power_in"))
      (node (ref "U6") (pin "99") (pinfunction "AGND_99") (pintype "power_in"))
      (node (ref "U7") (pin "11") (pinfunction "GND_11") (pintype "bidirectional"))
      (node (ref "U8") (pin "4") (pinfunction "VSS_4") (pintype "bidirectional"))
      (node (ref "U9") (pin "1") (pinfunction "REF_1") (pintype "input"))
      (node (ref "U9") (pin "2") (pinfunction "GND_2") (pintype "power_in"))
    )
    (net (code "125") (name "Net-(C5-Pad1)") (class "Default")
      (node (ref "C5") (pin "1") (pinfunction "1_1") (pintype "passive"))
      (node (ref "FB1") (pin "2") (pinfunction "2_2") (pintype "passive"))
      (node (ref "R3") (pin "2") (pinfunction "2_2") (pintype "passive"))
    )
    (net (code "126") (name "Net-(D1-C)") (class "Default")
      (node (ref "D1") (pin "4") (pinfunction "C_4") (pintype "passive"))
      (node (ref "R1") (pin "1") (pinfunction "1_1") (pintype "passive"))
      (node (ref "U2") (pin "4") (pinfunction "IN+_4") (pintype "input"))
    )
    (net (code "127") (name "Net-(D2-C)") (class "Default")
      (node (ref "D2") (pin "4") (pinfunction "C_4") (pintype "passive"))
      (node (ref "R2") (pin "1") (pinfunction "1_1") (pintype "passive"))
      (node (ref "U1") (pin "4") (pinfunction "IN+_4") (pintype "input"))
    )
    (net (code "128") (name "Net-(J7A-S)") (class "Default")
      (node (ref "J7") (pin "1") (pinfunction "S_1") (pintype "passive"))
      (node (ref "J8") (pin "P11") (pinfunction "1_P11") (pintype "passive"))
      (node (ref "J8") (pin "P14") (pinfunction "1_P14") (pintype "passive"))
      (node (ref "J8") (pin "P17") (pinfunction "1_P17") (pintype "passive"))
      (node (ref "J8") (pin "P2") (pinfunction "1_P2") (pintype "passive"))
      (node (ref "J8") (pin "P5") (pinfunction "1_P5") (pintype "passive"))
      (node (ref "J8") (pin "P8") (pinfunction "1_P8") (pintype "passive"))
    )
    (net (code "129") (name "Net-(J11A-S)") (class "Default")
      (node (ref "D3") (pin "C") (pinfunction "C_C") (pintype "passive"))
      (node (ref "D4") (pin "C") (pinfunction "C_C") (pintype "passive"))
      (node (ref "D5") (pin "C") (pinfunction "C_C") (pintype "passive"))
      (node (ref "J11") (pin "1") (pinfunction "S_1") (pintype "passive"))
      (node (ref "Q1") (pin "1") (pinfunction "S_1") (pintype "passive"))
      (node (ref "Q1") (pin "2") (pinfunction "S_2") (pintype "passive"))
      (node (ref "Q1") (pin "3") (pinfunction "S_3") (pintype "passive"))
      (node (ref "Q3") (pin "1") (pinfunction "S_1") (pintype "passive"))
      (node (ref "Q3") (pin "2") (pinfunction "S_2") (pintype "passive"))
      (node (ref "Q3") (pin "3") (pinfunction "S_3") (pintype "passive"))
      (node (ref "R1") (pin "2") (pinfunction "2_2") (pintype "passive"))
      (node (ref "R2") (pin "2") (pinfunction "2_2") (pintype "passive"))
      (node (ref "R4") (pin "2") (pinfunction "2_2") (pintype "passive"))
      (node (ref "R6") (pin "2") (pinfunction "2_2") (pintype "passive"))
      (node (ref "U1") (pin "5") (pinfunction "IN-_5") (pintype "input"))
      (node (ref "U2") (pin "5") (pinfunction "IN-_5") (pintype "input"))
    )
    (net (code "130") (name "Net-(J12A-S)") (class "Default")
      (node (ref "C35") (pin "1") (pinfunction "1_1") (pintype "passive"))
      (node (ref "J12") (pin "1") (pinfunction "S_1") (pintype "passive"))
      (node (ref "OC1") (pin "4") (pinfunction "C_4") (pintype "passive"))
      (node (ref "R8") (pin "1") (pinfunction "1_1") (pintype "passive"))
    )
    (net (code "131") (name "Net-(J14E-S)") (class "Default")
      (node (ref "J14") (pin "1") (pinfunction "S_1") (pintype "passive"))
      (node (ref "R59") (pin "2") (pinfunction "2_2") (pintype "passive"))
      (node (ref "U9") (pin "5") (pinfunction "IN-_5") (pintype "input"))
    )
    (net (code "132") (name "Net-(J15E-S)") (class "Default")
      (node (ref "J15") (pin "1") (pinfunction "S_1") (pintype "passive"))
      (node (ref "R60") (pin "2") (pinfunction "2_2") (pintype "passive"))
      (node (ref "U10") (pin "5") (pinfunction "IN-_5") (pintype "input"))
    )
    (net (code "133") (name "Net-(J16E-S)") (class "Default")
      (node (ref "J16") (pin "1") (pinfunction "S_1") (pintype "passive"))
      (node (ref "R61") (pin "2") (pinfunction "2_2") (pintype "passive"))
      (node (ref "U11") (pin "5") (pinfunction "IN-_5") (pintype "input"))
    )
    (net (code "134") (name "Net-(J17A-S)") (class "Default")
      (node (ref "J17") (pin "1") (pinfunction "S_1") (pintype "passive"))
      (node (ref "Q2") (pin "3") (pinfunction "D_3") (pintype "passive"))
      (node (ref "R9") (pin "1") (pinfunction "1_1") (pintype "passive"))
    )
    (net (code "135") (name "Net-(L1-1)") (class "Default")
      (node (ref "C12") (pin "2") (pinfunction "2_2") (pintype "passive"))
      (node (ref "D6") (pin "C") (pinfunction "C_C") (pintype "passive"))
      (node (ref "L1") (pin "P$1") (pinfunction "1_P$1") (pintype "passive"))
      (node (ref "U4") (pin "9") (pinfunction "SW_9") (pintype "bidirectional"))
    )
    (net (code "136") (name "Net-(LED1-PadA)") (class "Default")
      (node (ref "LED1") (pin "A") (pinfunction "A_A") (pintype "passive"))
      (node (ref "R18") (pin "2") (pinfunction "2_2") (pintype "passive"))
    )
    (net (code "137") (name "Net-(LED2-PadA)") (class "Default")
      (node (ref "LED2") (pin "A") (pinfunction "A_A") (pintype "passive"))
      (node (ref "R19") (pin "2") (pinfunction "2_2") (pintype "passive"))
    )
    (net (code "138") (name "Net-(LED3-PadC)") (class "Default")
      (node (ref "LED3") (pin "C") (pinfunction "C_C") (pintype "passive"))
      (node (ref "R21") (pin "1") (pinfunction "1_1") (pintype "passive"))
    )
    (net (code "139") (name "Net-(LED4-PadC)") (class "Default")
      (node (ref "LED4") (pin "C") (pinfunction "C_C") (pintype "passive"))
      (node (ref "R22") (pin "1") (pinfunction "1_1") (pintype "passive"))
    )
    (net (code "140") (name "Net-(LED5-PadA)") (class "Default")
      (node (ref "LED5") (pin "A") (pinfunction "A_A") (pintype "passive"))
      (node (ref "R23") (pin "2") (pinfunction "2_2") (pintype "passive"))
    )
    (net (code "141") (name "Net-(OC1-IN-A)") (class "Default")
      (node (ref "OC1") (pin "1") (pinfunction "IN-A_1") (pintype "passive"))
      (node (ref "R3") (pin "1") (pinfunction "1_1") (pintype "passive"))
    )
    (net (code "142") (name "Net-(Q1-G)") (class "Default")
      (node (ref "D4") (pin "A") (pinfunction "A_A") (pintype "passive"))
      (node (ref "Q1") (pin "4") (pinfunction "G_4") (pintype "passive"))
      (node (ref "R4") (pin "1") (pinfunction "1_1") (pintype "passive"))
      (node (ref "R8") (pin "2") (pinfunction "2_2") (pintype "passive"))
    )
    (net (code "143") (name "Net-(Q2-G)") (class "Default")
      (node (ref "Q2") (pin "1") (pinfunction "G_1") (pintype "passive"))
      (node (ref "R5") (pin "1") (pinfunction "1_1") (pintype "passive"))
      (node (ref "R7") (pin "1") (pinfunction "1_1") (pintype "passive"))
    )
    (net (code "144") (name "Net-(Q3-G)") (class "Default")
      (node (ref "D5") (pin "A") (pinfunction "A_A") (pintype "passive"))
      (node (ref "Q3") (pin "4") (pinfunction "G_4") (pintype "passive"))
      (node (ref "R6") (pin "1") (pinfunction "1_1") (pintype "passive"))
      (node (ref "R9") (pin "2") (pinfunction "2_2") (pintype "passive"))
    )
    (net (code "145") (name "Net-(Q4-G)") (class "Default")
      (node (ref "Q4") (pin "1") (pinfunction "G_1") (pintype "passive"))
      (node (ref "R36") (pin "2") (pinfunction "2_2") (pintype "passive"))
      (node (ref "R40") (pin "2") (pinfunction "2_2") (pintype "passive"))
    )
    (net (code "146") (name "Net-(Q5-G)") (class "Default")
      (node (ref "Q5") (pin "1") (pinfunction "G_1") (pintype "passive"))
      (node (ref "R37") (pin "2") (pinfunction "2_2") (pintype "passive"))
      (node (ref "R41") (pin "2") (pinfunction "2_2") (pintype "passive"))
    )
    (net (code "147") (name "Net-(Q6-G)") (class "Default")
      (node (ref "Q6") (pin "1") (pinfunction "G_1") (pintype "passive"))
      (node (ref "R38") (pin "2") (pinfunction "2_2") (pintype "passive"))
      (node (ref "R42") (pin "2") (pinfunction "2_2") (pintype "passive"))
    )
    (net (code "148") (name "Net-(Q7-G)") (class "Default")
      (node (ref "Q7") (pin "1") (pinfunction "G_1") (pintype "passive"))
      (node (ref "R39") (pin "2") (pinfunction "2_2") (pintype "passive"))
      (node (ref "R43") (pin "2") (pinfunction "2_2") (pintype "passive"))
    )
    (net (code "149") (name "Net-(SENS1-OUT)") (class "Default")
      (node (ref "R45") (pin "1") (pinfunction "1_1") (pintype "passive"))
      (node (ref "SENS1") (pin "2") (pinfunction "OUT_2") (pintype "output"))
    )
    (net (code "150") (name "Net-(SENS2-VOUT)") (class "Default")
      (node (ref "R44") (pin "1") (pinfunction "1_1") (pintype "passive"))
      (node (ref "SENS2") (pin "2") (pinfunction "VOUT_2") (pintype "output"))
    )
    (net (code "151") (name "Net-(TP1-P)") (class "Default")
      (node (ref "R52") (pin "1") (pinfunction "1_1") (pintype "passive"))
      (node (ref "TP1") (pin "1") (pinfunction "P_1") (pintype "passive"))
      (node (ref "U8") (pin "7") (pinfunction "WP_7") (pintype "bidirectional"))
    )
    (net (code "152") (name "Net-(TP20-P)") (class "Default")
      (node (ref "J5") (pin "20") (pinfunction "20_20") (pintype "passive"))
      (node (ref "TP20") (pin "1") (pinfunction "P_1") (pintype "passive"))
    )
    (net (code "153") (name "Net-(TP21-P)") (class "Default")
      (node (ref "J5") (pin "21") (pinfunction "21_21") (pintype "passive"))
      (node (ref "TP21") (pin "1") (pinfunction "P_1") (pintype "passive"))
    )
    (net (code "154") (name "Net-(TP22-P)") (class "Default")
      (node (ref "J5") (pin "22") (pinfunction "22_22") (pintype "passive"))
      (node (ref "TP22") (pin "1") (pinfunction "P_1") (pintype "passive"))
    )
    (net (code "155") (name "Net-(TP23-P)") (class "Default")
      (node (ref "J5") (pin "23") (pinfunction "23_23") (pintype "passive"))
      (node (ref "TP23") (pin "1") (pinfunction "P_1") (pintype "passive"))
    )
    (net (code "156") (name "Net-(TP24-P)") (class "Default")
      (node (ref "J5") (pin "24") (pinfunction "24_24") (pintype "passive"))
      (node (ref "TP24") (pin "1") (pinfunction "P_1") (pintype "passive"))
    )
    (net (code "157") (name "Net-(TP25-P)") (class "Default")
      (node (ref "J5") (pin "25") (pinfunction "25_25") (pintype "passive"))
      (node (ref "TP25") (pin "1") (pinfunction "P_1") (pintype "passive"))
    )
    (net (code "158") (name "Net-(U3-IN+)") (class "Default")
      (node (ref "Q1") (pin "5") (pinfunction "D_5") (pintype "passive"))
      (node (ref "Q1") (pin "6") (pinfunction "D_6") (pintype "passive"))
      (node (ref "Q1") (pin "7") (pinfunction "D_7") (pintype "passive"))
      (node (ref "Q1") (pin "8") (pinfunction "D_8") (pintype "passive"))
      (node (ref "R10") (pin "1") (pinfunction "1_1") (pintype "passive"))
      (node (ref "R12") (pin "1") (pinfunction "1_1") (pintype "passive"))
      (node (ref "U3") (pin "4") (pinfunction "IN+_4") (pintype "input"))
    )
    (net (code "159") (name "Net-(U4-BST)") (class "Default")
      (node (ref "C12") (pin "1") (pinfunction "1_1") (pintype "passive"))
      (node (ref "U4") (pin "10") (pinfunction "BST_10") (pintype "bidirectional"))
    )
    (net (code "160") (name "Net-(U4-CS)") (class "Default")
      (node (ref "D6") (pin "A") (pinfunction "A_A") (pintype "passive"))
      (node (ref "R15") (pin "2") (pinfunction "2_2") (pintype "passive"))
      (node (ref "U4") (pin "8") (pinfunction "CS_8") (pintype "bidirectional"))
    )
    (net (code "161") (name "Net-(U4-FB)") (class "Default")
      (node (ref "R16") (pin "1") (pinfunction "1_1") (pintype "passive"))
      (node (ref "R17") (pin "2") (pinfunction "2_2") (pintype "passive"))
      (node (ref "U4") (pin "6") (pinfunction "FB_6") (pintype "bidirectional"))
    )
    (net (code "162") (name "Net-(U4-PGD)") (class "Default")
      (node (ref "R13") (pin "1") (pinfunction "1_1") (pintype "passive"))
      (node (ref "U4") (pin "3") (pinfunction "PGD_3") (pintype "bidirectional"))
    )
    (net (code "163") (name "Net-(U4-RT)") (class "Default")
      (node (ref "R14") (pin "1") (pinfunction "1_1") (pintype "passive"))
      (node (ref "U4") (pin "2") (pinfunction "RT_2") (pintype "bidirectional"))
    )
    (net (code "164") (name "Net-(U4-SS)") (class "Default")
      (node (ref "C11") (pin "1") (pinfunction "1_1") (pintype "passive"))
      (node (ref "U4") (pin "4") (pinfunction "SS_4") (pintype "bidirectional"))
    )
    (net (code "165") (name "Net-(U4-VIN)") (class "Default")
      (node (ref "C10") (pin "1") (pinfunction "1_1") (pintype "passive"))
      (node (ref "C8") (pin "1") (pinfunction "1_1") (pintype "passive"))
      (node (ref "C9") (pin "1") (pinfunction "1_1") (pintype "passive"))
      (node (ref "F1") (pin "2") (pinfunction "2_2") (pintype "passive"))
      (node (ref "R14") (pin "2") (pinfunction "2_2") (pintype "passive"))
      (node (ref "U4") (pin "1") (pinfunction "VIN_1") (pintype "input"))
    )
    (net (code "166") (name "Net-(U6-XTAL1)") (class "Default")
      (node (ref "C20") (pin "1") (pinfunction "1_1") (pintype "passive"))
      (node (ref "U6") (pin "34") (pinfunction "XTAL1_34") (pintype "input"))
      (node (ref "X1") (pin "1") (pinfunction "1_1") (pintype "passive"))
    )
    (net (code "167") (name "Net-(U6-XTAL2)") (class "Default")
      (node (ref "C19") (pin "1") (pinfunction "1_1") (pintype "passive"))
      (node (ref "U6") (pin "33") (pinfunction "XTAL2_33") (pintype "output"))
      (node (ref "X1") (pin "2") (pinfunction "2_2") (pintype "passive"))
    )
    (net (code "168") (name "Net-(U7-A8)") (class "Default")
      (node (ref "R62") (pin "1") (pinfunction "1_1") (pintype "passive"))
      (node (ref "U7") (pin "9") (pinfunction "A8_9") (pintype "bidirectional"))
    )
    (net (code "169") (name "Net-(U7-OE)") (class "Default")
      (node (ref "R47") (pin "1") (pinfunction "1_1") (pintype "passive"))
      (node (ref "R48") (pin "1") (pinfunction "1_1") (pintype "passive"))
      (node (ref "U7") (pin "10") (pinfunction "OE_10") (pintype "bidirectional"))
    )
    (net (code "170") (name "Net-(U8-A0)") (class "Default")
      (node (ref "R49") (pin "1") (pinfunction "1_1") (pintype "passive"))
      (node (ref "S1") (pin "4") (pinfunction "4_4") (pintype "passive"))
      (node (ref "U8") (pin "1") (pinfunction "A0_1") (pintype "input"))
    )
    (net (code "171") (name "Net-(U8-A1)") (class "Default")
      (node (ref "R50") (pin "1") (pinfunction "1_1") (pintype "passive"))
      (node (ref "S1") (pin "3") (pinfunction "3_3") (pintype "passive"))
      (node (ref "U8") (pin "2") (pinfunction "A1_2") (pintype "input"))
    )
    (net (code "172") (name "Net-(U8-A2)") (class "Default")
      (node (ref "R51") (pin "1") (pinfunction "1_1") (pintype "passive"))
      (node (ref "U8") (pin "3") (pinfunction "A2_3") (pintype "input"))
    )
    (net (code "173") (name "PWM_1+") (class "Default")
      (node (ref "D7") (pin "C") (pinfunction "C_C") (pintype "passive"))
      (node (ref "J1") (pin "1") (pinfunction "1_1") (pintype "passive"))
      (node (ref "R24") (pin "2") (pinfunction "2_2") (pintype "passive"))
      (node (ref "R25") (pin "2") (pinfunction "2_2") (pintype "passive"))
      (node (ref "R26") (pin "2") (pinfunction "2_2") (pintype "passive"))
    )
    (net (code "174") (name "PWM_1-") (class "Default")
      (node (ref "D7") (pin "A") (pinfunction "A_A") (pintype "passive"))
      (node (ref "J1") (pin "2") (pinfunction "1_2") (pintype "passive"))
      (node (ref "Q4") (pin "3") (pinfunction "D_3") (pintype "passive"))
    )
    (net (code "175") (name "PWM_2+") (class "Default")
      (node (ref "D8") (pin "C") (pinfunction "C_C") (pintype "passive"))
      (node (ref "J1") (pin "3") (pinfunction "1_3") (pintype "passive"))
      (node (ref "R27") (pin "2") (pinfunction "2_2") (pintype "passive"))
      (node (ref "R28") (pin "2") (pinfunction "2_2") (pintype "passive"))
      (node (ref "R29") (pin "2") (pinfunction "2_2") (pintype "passive"))
    )
    (net (code "176") (name "PWM_2-") (class "Default")
      (node (ref "D8") (pin "A") (pinfunction "A_A") (pintype "passive"))
      (node (ref "J1") (pin "4") (pinfunction "1_4") (pintype "passive"))
      (node (ref "Q5") (pin "3") (pinfunction "D_3") (pintype "passive"))
    )
    (net (code "177") (name "PWM_3+") (class "Default")
      (node (ref "D9") (pin "C") (pinfunction "C_C") (pintype "passive"))
      (node (ref "J1") (pin "5") (pinfunction "1_5") (pintype "passive"))
      (node (ref "R30") (pin "2") (pinfunction "2_2") (pintype "passive"))
      (node (ref "R31") (pin "2") (pinfunction "2_2") (pintype "passive"))
      (node (ref "R32") (pin "2") (pinfunction "2_2") (pintype "passive"))
    )
    (net (code "178") (name "PWM_3-") (class "Default")
      (node (ref "D9") (pin "A") (pinfunction "A_A") (pintype "passive"))
      (node (ref "J1") (pin "6") (pinfunction "1_6") (pintype "passive"))
      (node (ref "Q6") (pin "3") (pinfunction "D_3") (pintype "passive"))
    )
    (net (code "179") (name "PWM_4+") (class "Default")
      (node (ref "D10") (pin "C") (pinfunction "C_C") (pintype "passive"))
      (node (ref "J1") (pin "7") (pinfunction "1_7") (pintype "passive"))
      (node (ref "R33") (pin "2") (pinfunction "2_2") (pintype "passive"))
      (node (ref "R34") (pin "2") (pinfunction "2_2") (pintype "passive"))
      (node (ref "R35") (pin "2") (pinfunction "2_2") (pintype "passive"))
    )
    (net (code "180") (name "PWM_4-") (class "Default")
      (node (ref "D10") (pin "A") (pinfunction "A_A") (pintype "passive"))
      (node (ref "J1") (pin "8") (pinfunction "1_8") (pintype "passive"))
      (node (ref "Q7") (pin "3") (pinfunction "D_3") (pintype "passive"))
    )
    (net (code "181") (name "RESET_N") (class "Default")
      (node (ref "J13") (pin "5") (pinfunction "5_5") (pintype "passive"))
      (node (ref "R20") (pin "2") (pinfunction "2_2") (pintype "passive"))
      (node (ref "U6") (pin "30") (pinfunction "RESET_30") (pintype "input"))
      (node (ref "U7") (pin "13") (pinfunction "B7_13") (pintype "bidirectional"))
    )
    (net (code "182") (name "TETHER_A") (class "Default")
      (node (ref "FB1") (pin "1") (pinfunction "1_1") (pintype "passive"))
      (node (ref "J10") (pin "1") (pinfunction "S_1") (pintype "passive"))
      (node (ref "J5") (pin "18") (pinfunction "18_18") (pintype "passive"))
    )
    (net (code "183") (name "TETHER_B") (class "Default")
      (node (ref "C5") (pin "2") (pinfunction "2_2") (pintype "passive"))
      (node (ref "J10") (pin "3") (pinfunction "S_3") (pintype "passive"))
      (node (ref "J5") (pin "19") (pinfunction "19_19") (pintype "passive"))
      (node (ref "OC1") (pin "2") (pinfunction "IN-B_2") (pintype "passive"))
    )
    (net (code "184") (name "V_BAT") (class "Default")
      (node (ref "F1") (pin "1") (pinfunction "1_1") (pintype "passive"))
      (node (ref "R12") (pin "2") (pinfunction "2_2") (pintype "passive"))
      (node (ref "R26") (pin "1") (pinfunction "1_1") (pintype "passive"))
      (node (ref "R29") (pin "1") (pinfunction "1_1") (pintype "passive"))
      (node (ref "R32") (pin "1") (pinfunction "1_1") (pintype "passive"))
      (node (ref "R35") (pin "1") (pinfunction "1_1") (pintype "passive"))
      (node (ref "U3") (pin "5") (pinfunction "IN-_5") (pintype "input"))
    )
    (net (code "185") (name "unconnected-(J10B-S-Pad2)") (class "Default")
      (node (ref "J10") (pin "2") (pinfunction "S_2") (pintype "passive"))
    )
    (net (code "186") (name "unconnected-(U6-(CLKO{slash}ICP3{slash}INT7)PE7-Pad9)") (class "Default")
      (node (ref "U6") (pin "9") (pinfunction "(CLKO/ICP3/INT7)PE7_9") (pintype "bidirectional"))
    )
    (net (code "187") (name "unconnected-(U6-(ICP1)PD4-Pad47)") (class "Default")
      (node (ref "U6") (pin "47") (pinfunction "(ICP1)PD4_47") (pintype "bidirectional"))
    )
    (net (code "188") (name "unconnected-(U6-(T1)PD6-Pad49)") (class "Default")
      (node (ref "U6") (pin "49") (pinfunction "(T1)PD6_49") (pintype "bidirectional"))
    )
    (net (code "189") (name "unconnected-(U6-(T3{slash}INT6)PE6-Pad8)") (class "Default")
      (node (ref "U6") (pin "8") (pinfunction "(T3/INT6)PE6_8") (pintype "bidirectional"))
    )
    (net (code "190") (name "unconnected-(U6-(TOSC1)PG4-Pad29)") (class "Default")
      (node (ref "U6") (pin "29") (pinfunction "(TOSC1)PG4_29") (pintype "bidirectional"))
    )
    (net (code "191") (name "unconnected-(U6-(TOSC2)PG3-Pad28)") (class "Default")
      (node (ref "U6") (pin "28") (pinfunction "(TOSC2)PG3_28") (pintype "bidirectional"))
    )
    (net (code "192") (name "unconnected-(U6-(XCK0{slash}AIN0)PE2-Pad4)") (class "Default")
      (node (ref "U6") (pin "4") (pinfunction "(XCK0/AIN0)PE2_4") (pintype "bidirectional"))
    )
    (net (code "193") (name "unconnected-(U6-(XCK1)PD5-Pad48)") (class "Default")
      (node (ref "U6") (pin "48") (pinfunction "(XCK1)PD5_48") (pintype "bidirectional"))
    )
    (net (code "194") (name "unconnected-(U6-PH2(XCK2)-Pad14)") (class "Default")
      (node (ref "U6") (pin "14") (pinfunction "PH2(XCK2)_14") (pintype "bidirectional"))
    )
    (net (code "195") (name "unconnected-(U6-PH7(T4)-Pad27)") (class "Default")
      (node (ref "U6") (pin "27") (pinfunction "PH7(T4)_27") (pintype "bidirectional"))
    )
    (net (code "196") (name "unconnected-(U6-PJ2(XCK3{slash}PCINT11)-Pad65)") (class "Default")
      (node (ref "U6") (pin "65") (pinfunction "PJ2(XCK3/PCINT11)_65") (pintype "bidirectional"))
    )
    (net (code "197") (name "unconnected-(U6-PJ3(PCINT12)-Pad66)") (class "Default")
      (node (ref "U6") (pin "66") (pinfunction "PJ3(PCINT12)_66") (pintype "bidirectional"))
    )
    (net (code "198") (name "unconnected-(U6-PJ4(PCINT13)-Pad67)") (class "Default")
      (node (ref "U6") (pin "67") (pinfunction "PJ4(PCINT13)_67") (pintype "bidirectional"))
    )
    (net (code "199") (name "unconnected-(U6-PJ5(PCINT14)-Pad68)") (class "Default")
      (node (ref "U6") (pin "68") (pinfunction "PJ5(PCINT14)_68") (pintype "bidirectional"))
    )
    (net (code "200") (name "unconnected-(U6-PJ6(PCINT15)-Pad69)") (class "Default")
      (node (ref "U6") (pin "69") (pinfunction "PJ6(PCINT15)_69") (pintype "bidirectional"))
    )
    (net (code "201") (name "unconnected-(U6-PJ7-Pad79)") (class "Default")
      (node (ref "U6") (pin "79") (pinfunction "PJ7_79") (pintype "bidirectional"))
    )
    (net (code "202") (name "unconnected-(U7-B8-Pad12)") (class "Default")
      (node (ref "U7") (pin "12") (pinfunction "B8_12") (pintype "bidirectional"))
    )
  )
)
